# ProPrj_keero_bot_2026-04-02.net
KiCad netlist of a schematic drawn in EasyEDA Pro
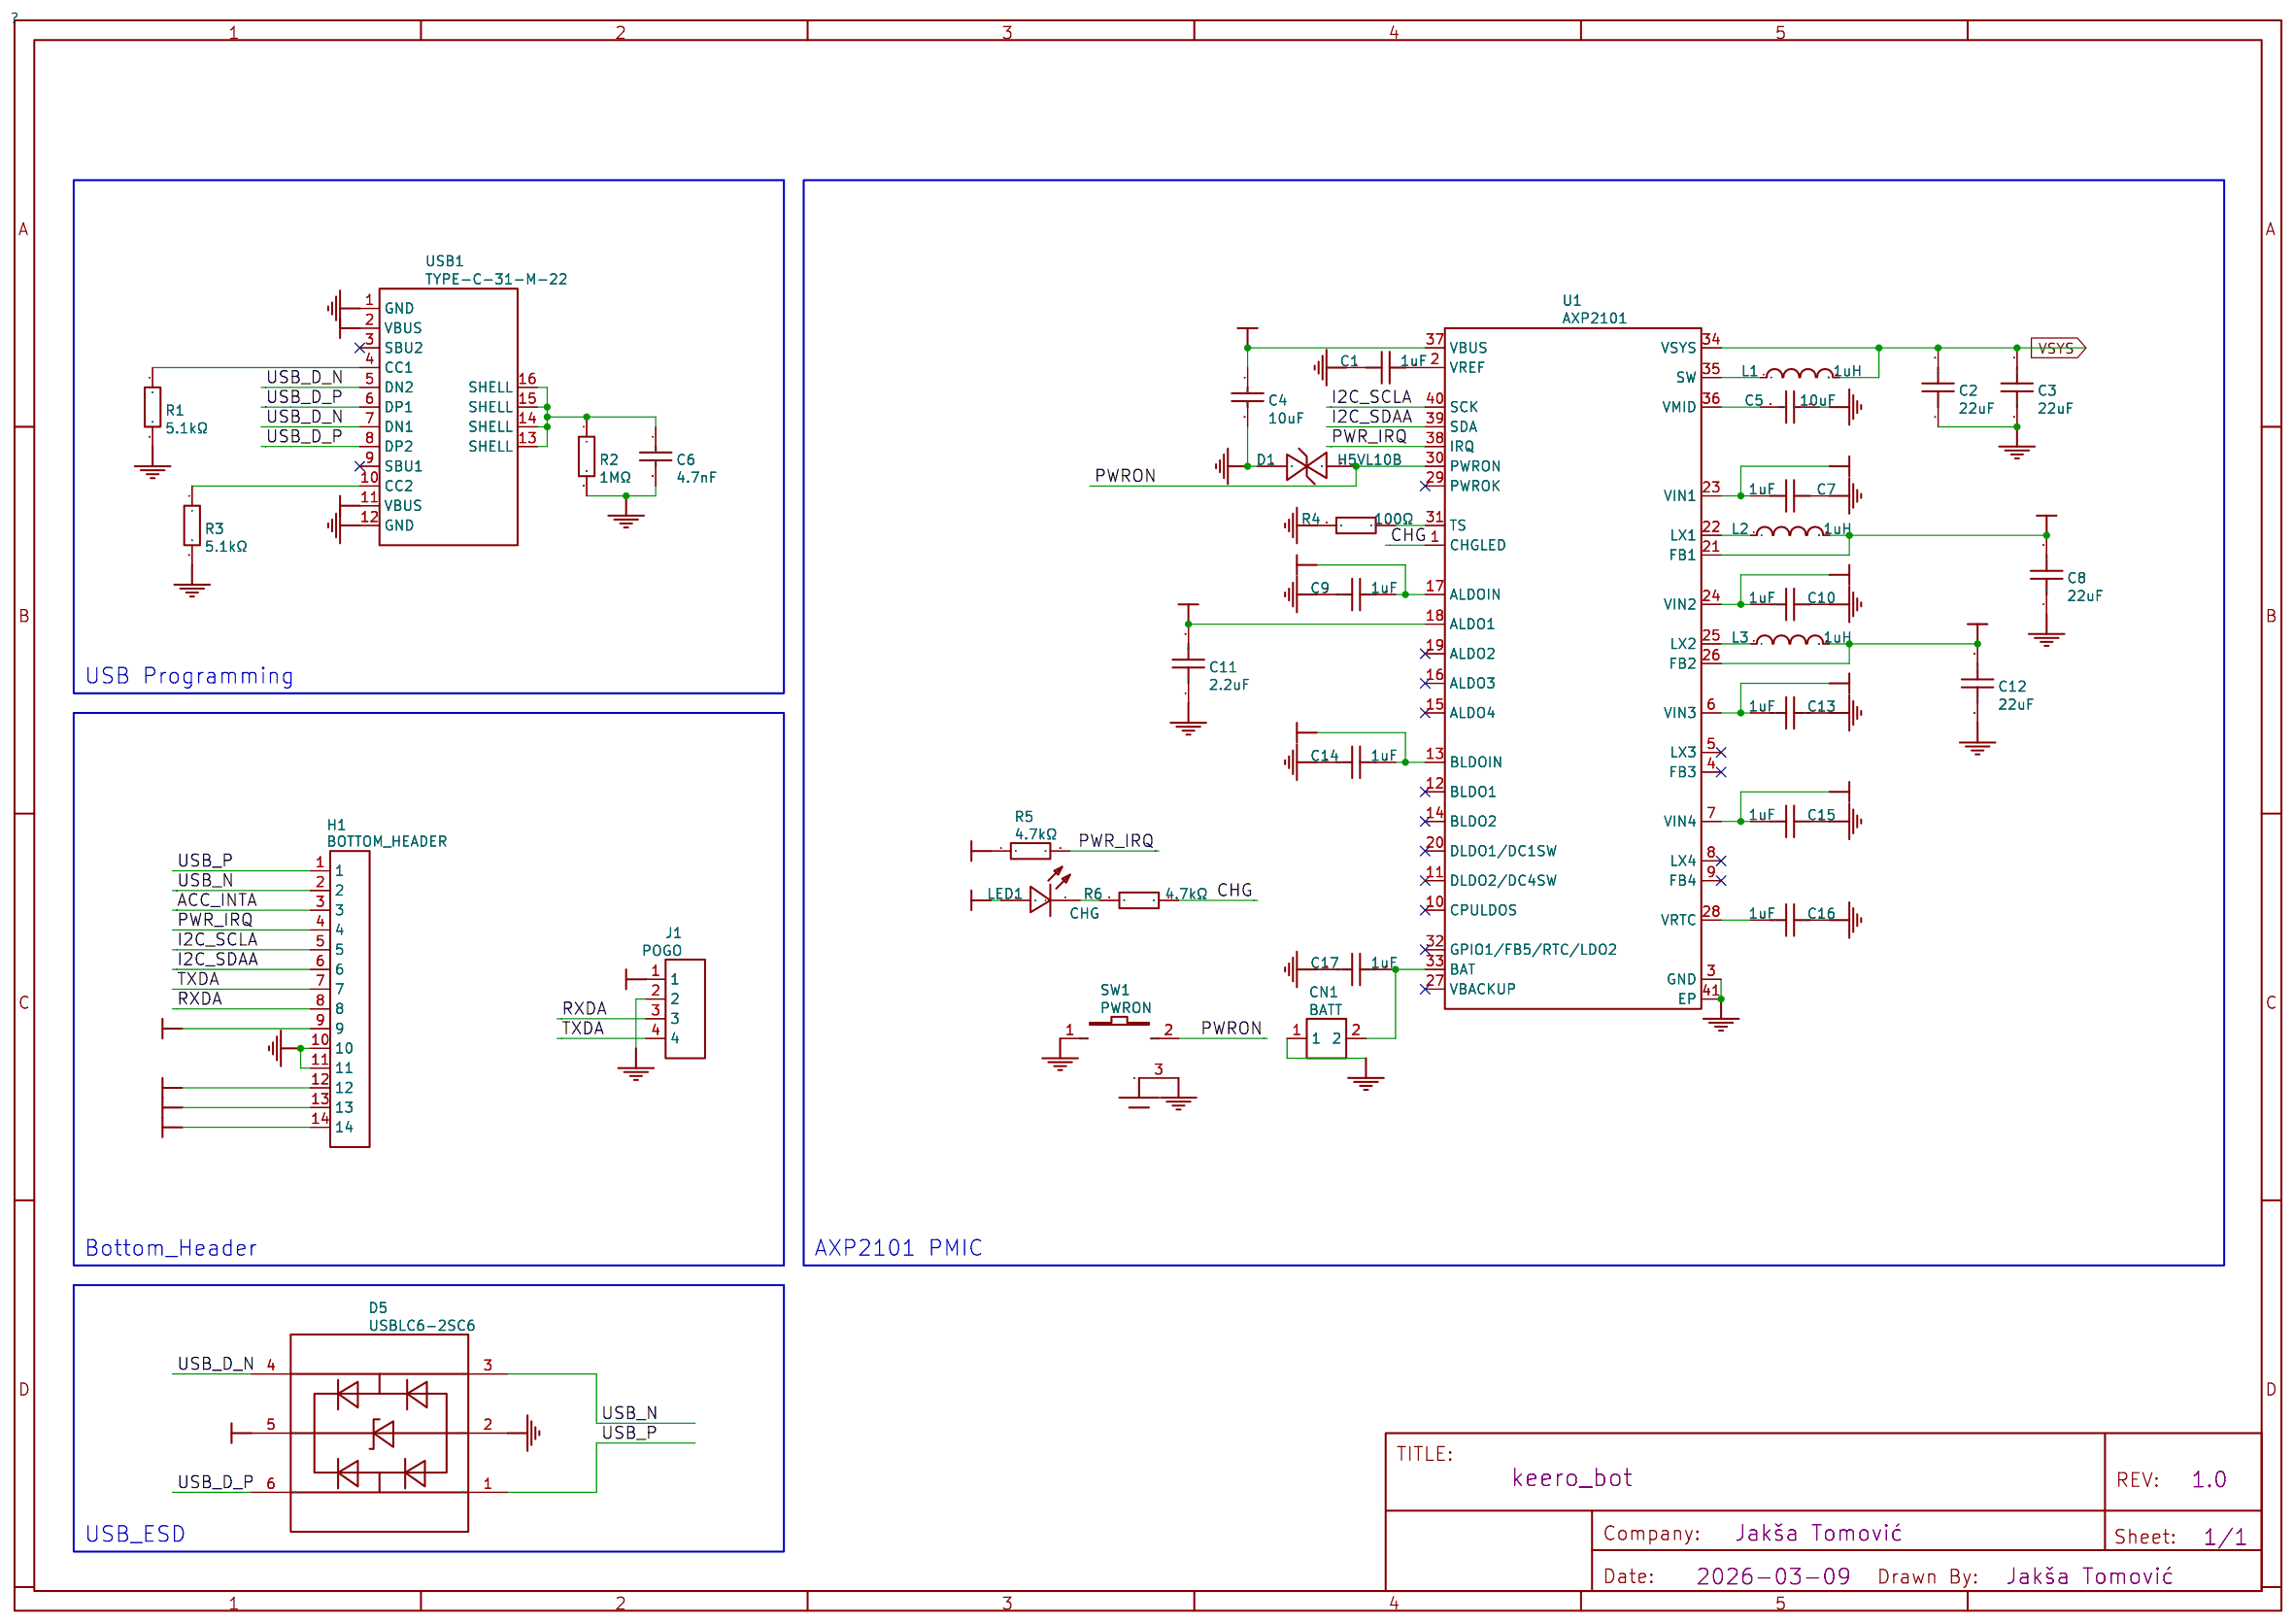
[diagram p0: Power_Sheet]
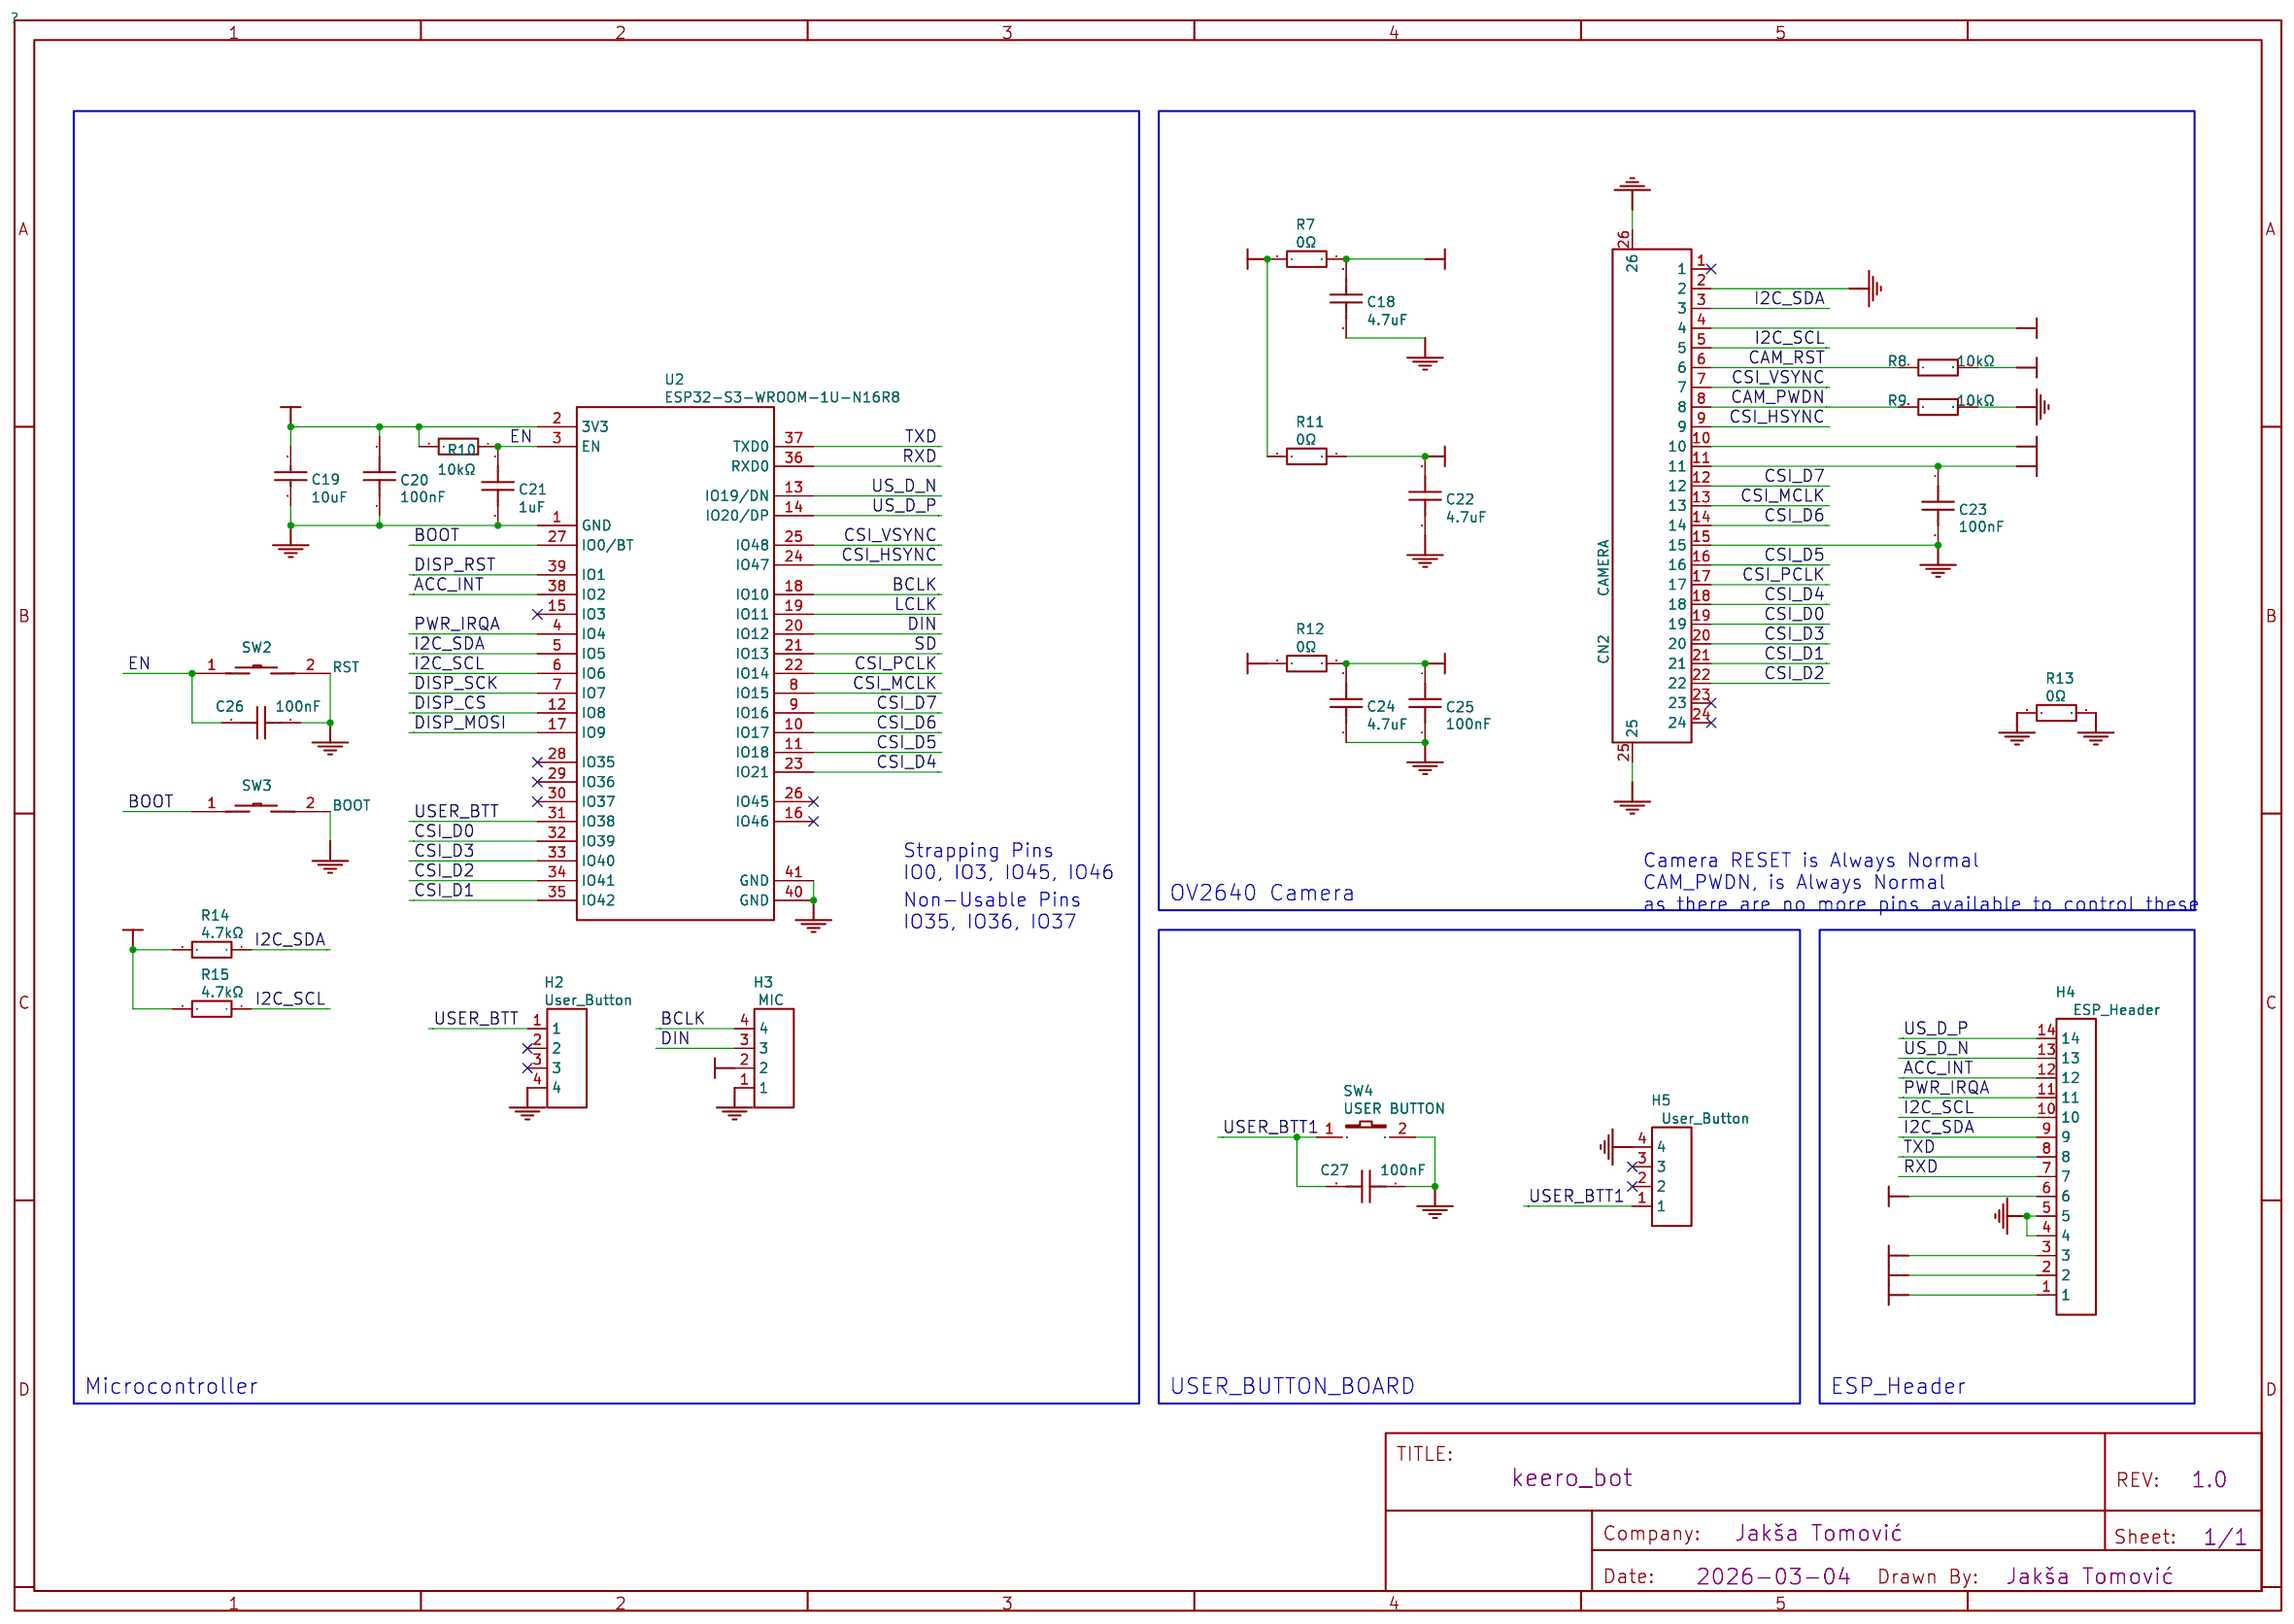
[diagram p1: MCU_Sheet]
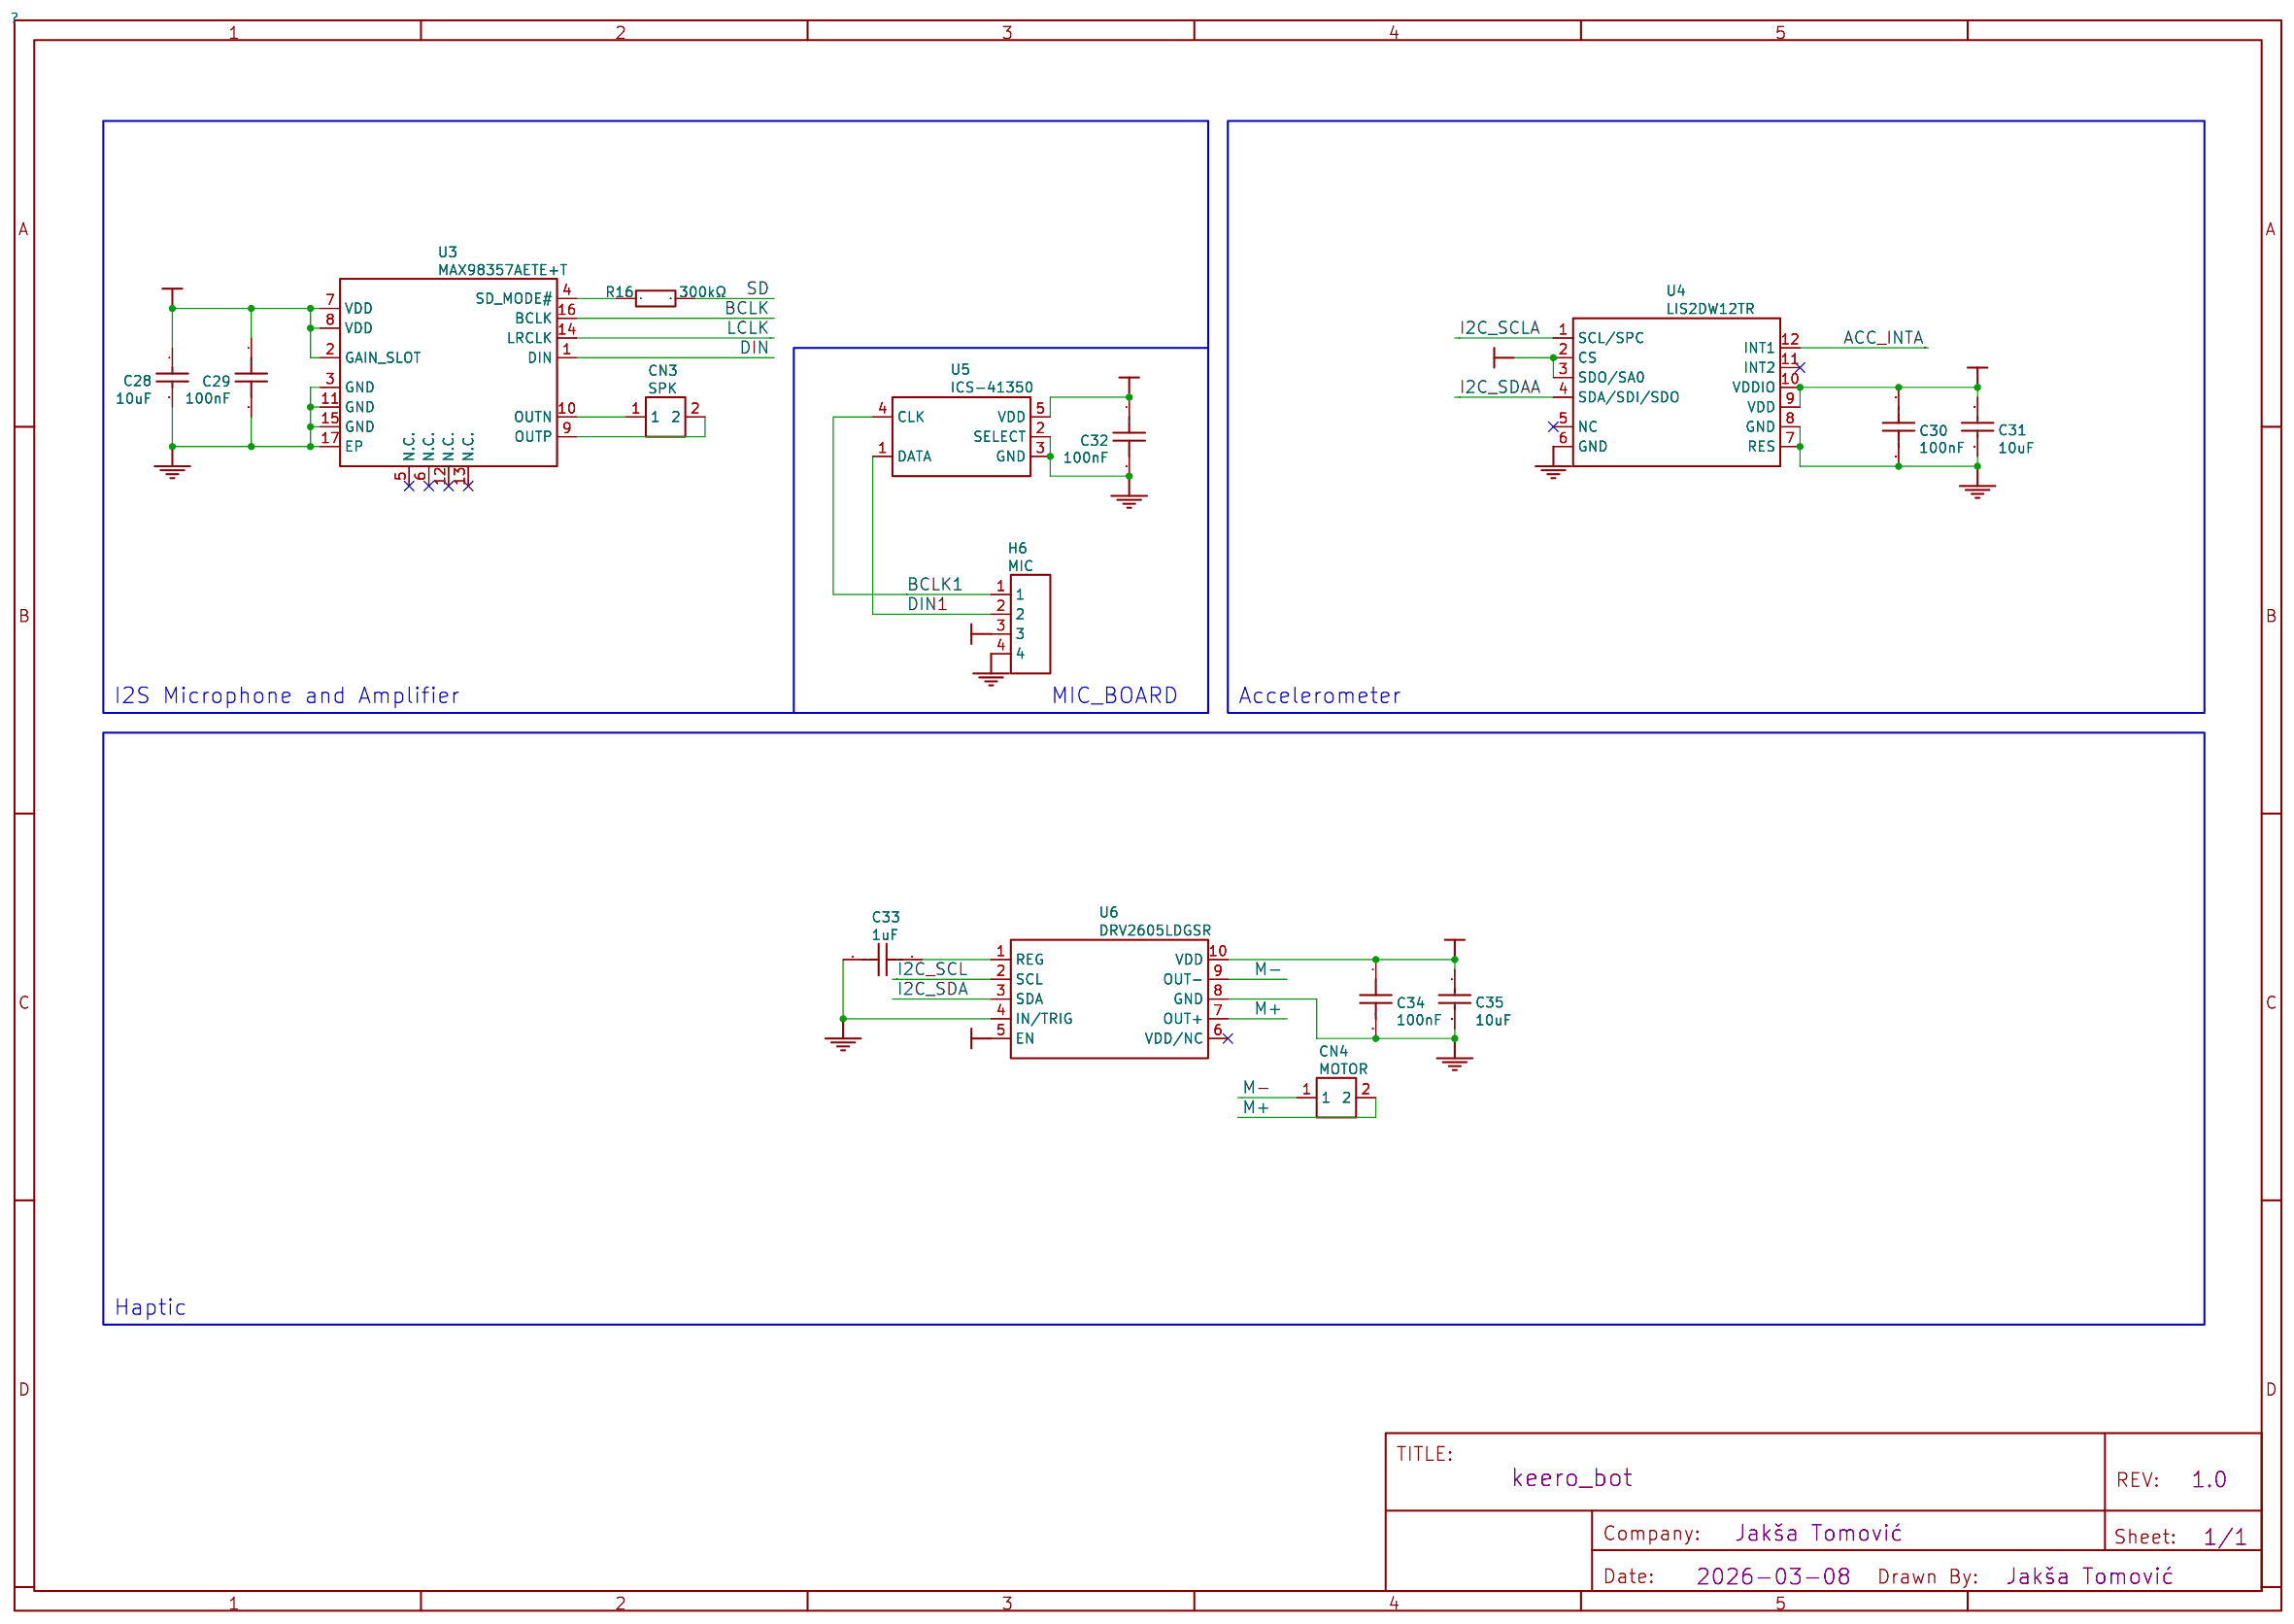
[diagram p2: Sensor_Sheet]
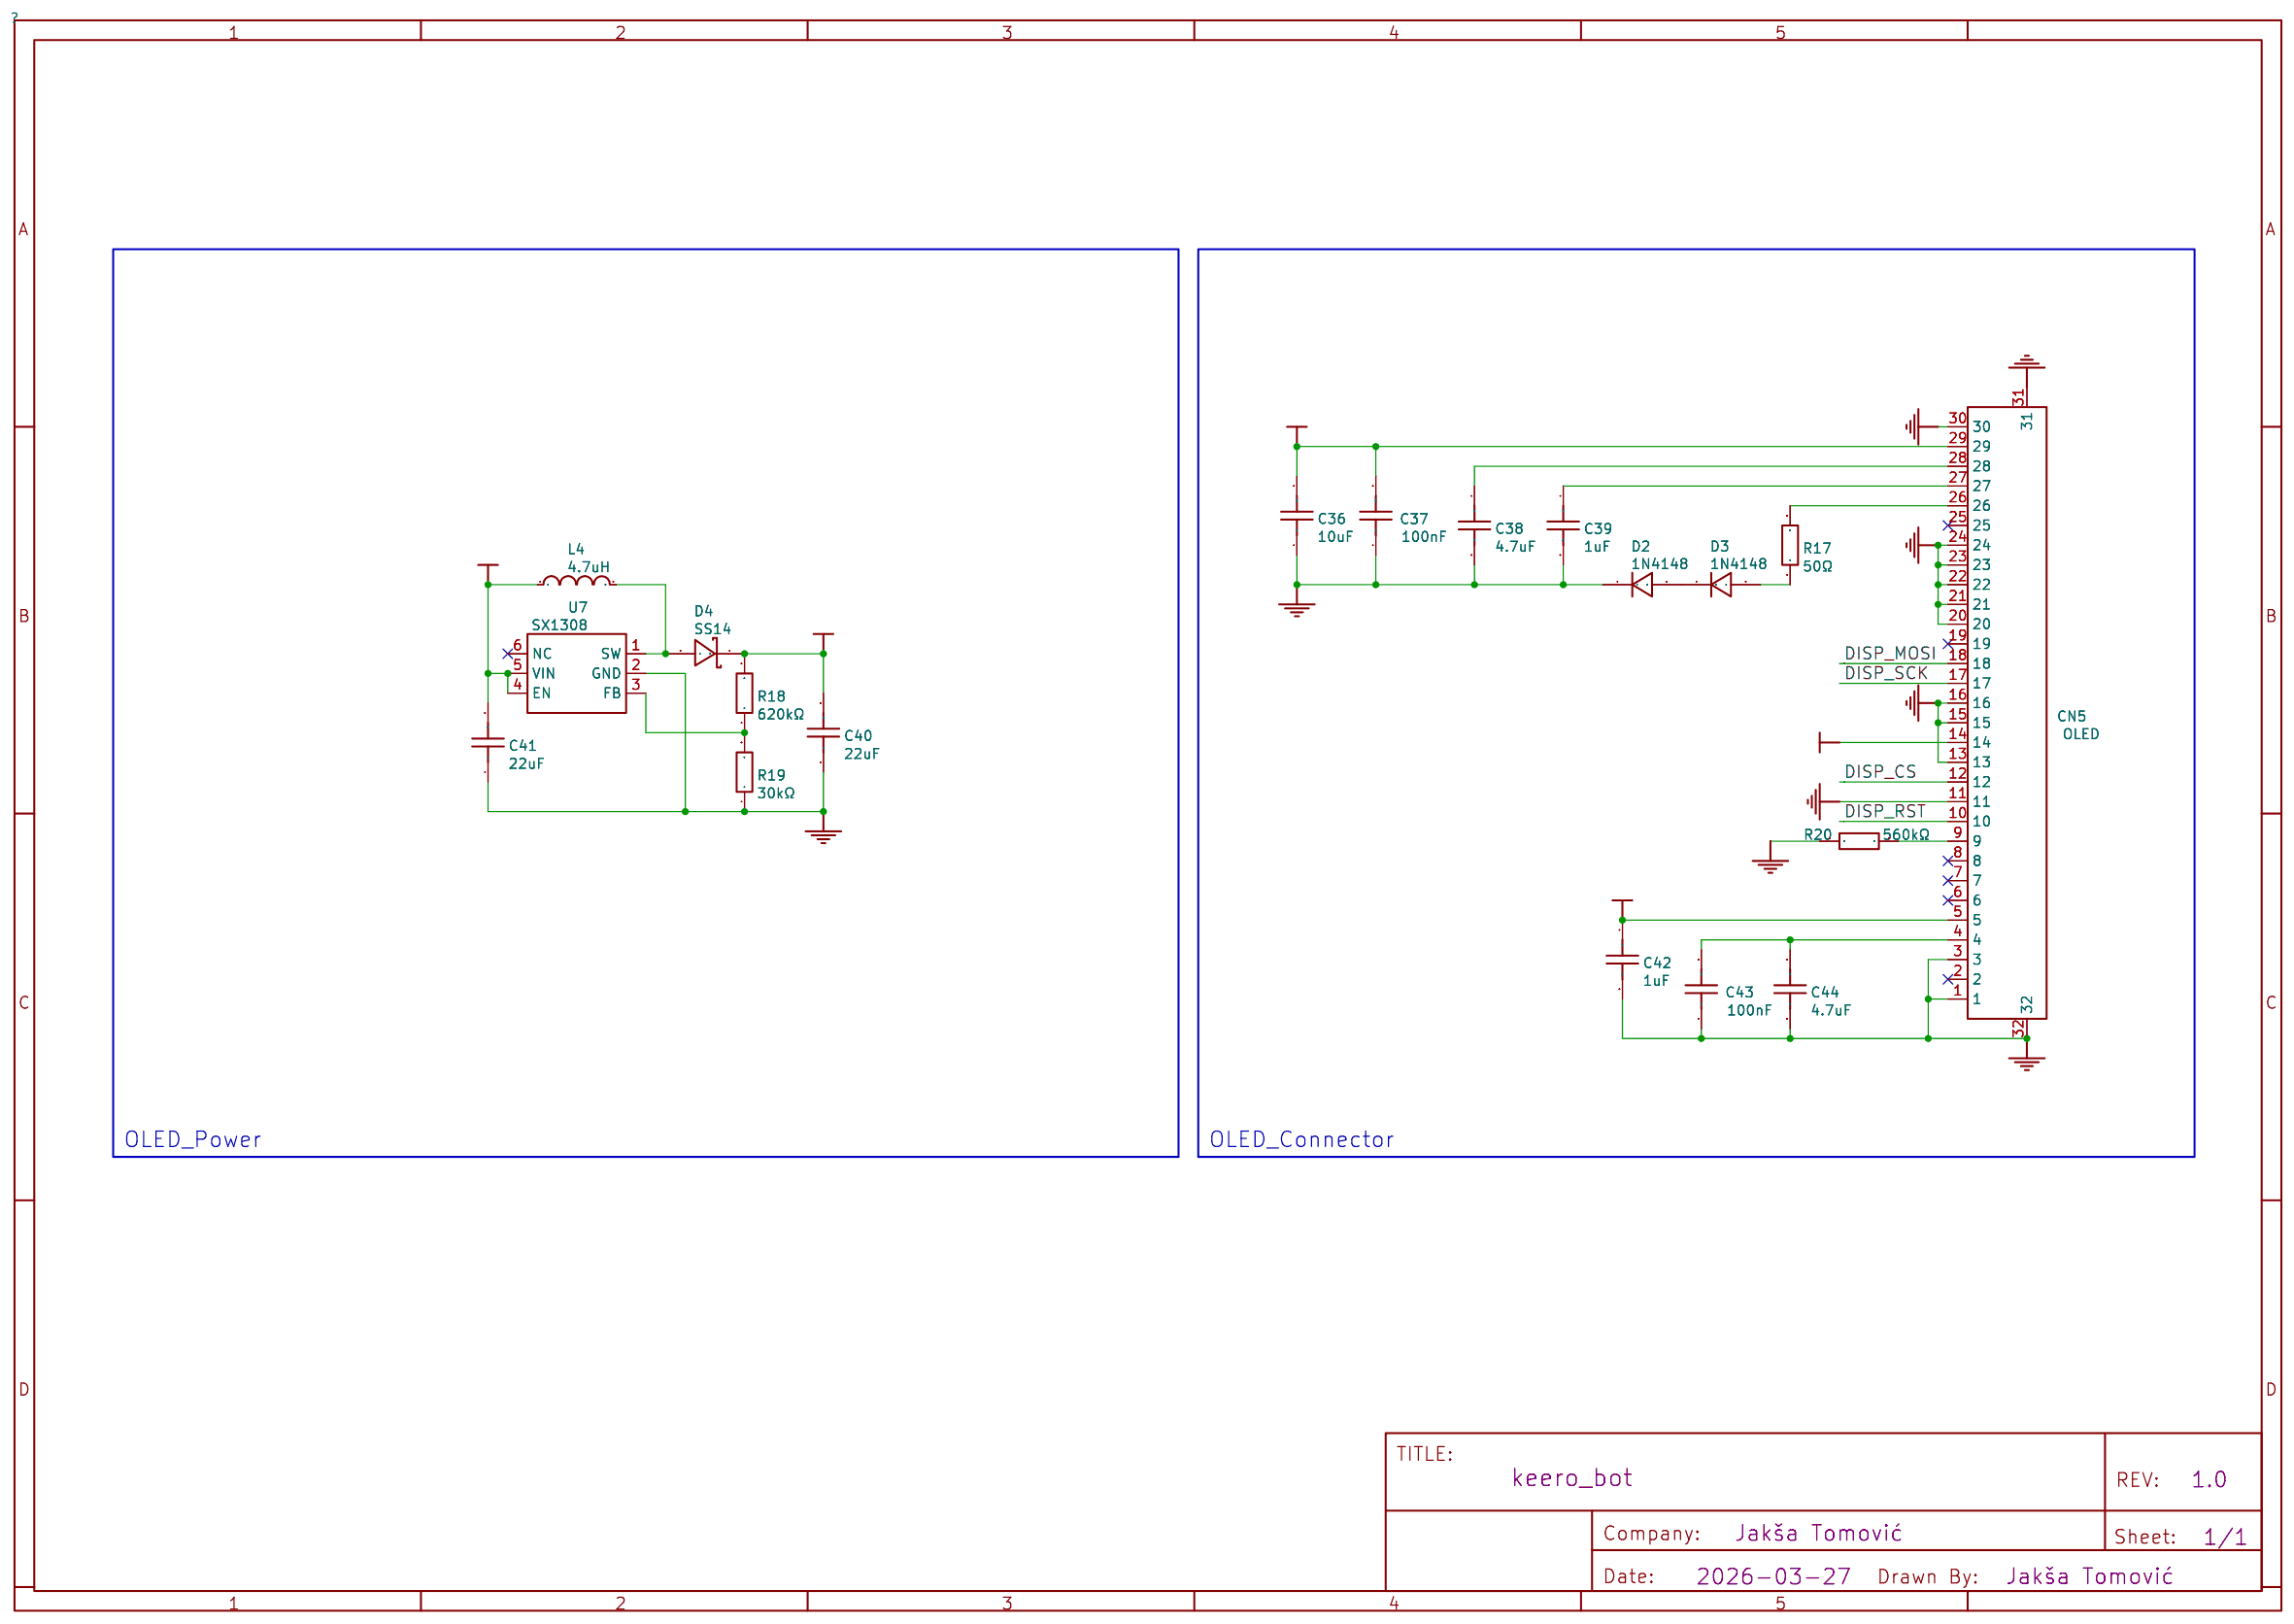
[diagram p3: OLED_Sheet]

(export (version "E")
  (design (tool "Eeschema 10.0.6"))
  (components
    (comp (ref "C1")
      (value "1uF")
      (footprint "easyedapro:C0402")
      (fields
        (field (name "Manufacturer Part") "CL05A105KA5NQNC")
        (field (name "Manufacturer") "SAMSUNG(三星)")
      )
      (libsource (lib "") (part "1uF_1"))
    )
    (comp (ref "C2")
      (value "22uF")
      (footprint "easyedapro:C0402_NEW")
      (fields
        (field (name "Manufacturer Part") "CL05A226MQ5QUNC")
        (field (name "Manufacturer") "SAMSUNG(三星)")
        (field (name "Contributor") "lcsc")
      )
      (libsource (lib "easyedapro") (part "22uF"))
    )
    (comp (ref "C3")
      (value "22uF")
      (footprint "easyedapro:C0402_NEW")
      (fields
        (field (name "Manufacturer Part") "CL05A226MQ5QUNC")
        (field (name "Manufacturer") "SAMSUNG(三星)")
        (field (name "Contributor") "lcsc")
      )
      (libsource (lib "easyedapro") (part "22uF"))
    )
    (comp (ref "C4")
      (value "10uF")
      (footprint "easyedapro:C0402")
      (fields
        (field (name "Manufacturer Part") "CL05A106MQ5NUNC")
        (field (name "Manufacturer") "SAMSUNG(三星)")
      )
      (libsource (lib "easyedapro") (part "10uF"))
    )
    (comp (ref "C5")
      (value "10uF")
      (footprint "easyedapro:C0402")
      (fields
        (field (name "Manufacturer Part") "CL05A106MQ5NUNC")
        (field (name "Manufacturer") "SAMSUNG(三星)")
      )
      (libsource (lib "easyedapro") (part "10uF"))
    )
    (comp (ref "C6")
      (value "4.7nF")
      (footprint "easyedapro:C0402")
      (fields (field (name "Manufacturer Part") "0402B472K500NT") (field (name "Manufacturer") "FH(风华)"))
      (libsource (lib "easyedapro") (part "4.7nF"))
    )
    (comp (ref "C7")
      (value "1uF")
      (footprint "easyedapro:C0402")
      (fields
        (field (name "Manufacturer Part") "CL05A105KA5NQNC")
        (field (name "Manufacturer") "SAMSUNG(三星)")
      )
      (libsource (lib "easyedapro") (part "1uF"))
    )
    (comp (ref "C8")
      (value "22uF")
      (footprint "easyedapro:C0402_NEW")
      (fields
        (field (name "Manufacturer Part") "CL05A226MQ5QUNC")
        (field (name "Manufacturer") "SAMSUNG(三星)")
        (field (name "Contributor") "lcsc")
      )
      (libsource (lib "easyedapro") (part "22uF"))
    )
    (comp (ref "C9")
      (value "1uF")
      (footprint "easyedapro:C0402")
      (fields
        (field (name "Manufacturer Part") "CL05A105KA5NQNC")
        (field (name "Manufacturer") "SAMSUNG(三星)")
      )
      (libsource (lib "") (part "1uF_1"))
    )
    (comp (ref "C10")
      (value "1uF")
      (footprint "easyedapro:C0402")
      (fields
        (field (name "Manufacturer Part") "CL05A105KA5NQNC")
        (field (name "Manufacturer") "SAMSUNG(三星)")
      )
      (libsource (lib "easyedapro") (part "1uF"))
    )
    (comp (ref "C11")
      (value "2.2uF")
      (footprint "easyedapro:C0402")
      (fields
        (field (name "Manufacturer Part") "CL05A225MQ5NSNC")
        (field (name "Manufacturer") "SAMSUNG(三星)")
      )
      (libsource (lib "easyedapro") (part "2.2uF"))
    )
    (comp (ref "C12")
      (value "22uF")
      (footprint "easyedapro:C0402_NEW")
      (fields
        (field (name "Manufacturer Part") "CL05A226MQ5QUNC")
        (field (name "Manufacturer") "SAMSUNG(三星)")
        (field (name "Contributor") "lcsc")
      )
      (libsource (lib "easyedapro") (part "22uF"))
    )
    (comp (ref "C13")
      (value "1uF")
      (footprint "easyedapro:C0402")
      (fields
        (field (name "Manufacturer Part") "CL05A105KA5NQNC")
        (field (name "Manufacturer") "SAMSUNG(三星)")
      )
      (libsource (lib "easyedapro") (part "1uF"))
    )
    (comp (ref "C14")
      (value "1uF")
      (footprint "easyedapro:C0402")
      (fields
        (field (name "Manufacturer Part") "CL05A105KA5NQNC")
        (field (name "Manufacturer") "SAMSUNG(三星)")
      )
      (libsource (lib "") (part "1uF_1"))
    )
    (comp (ref "C15")
      (value "1uF")
      (footprint "easyedapro:C0402")
      (fields
        (field (name "Manufacturer Part") "CL05A105KA5NQNC")
        (field (name "Manufacturer") "SAMSUNG(三星)")
      )
      (libsource (lib "easyedapro") (part "1uF"))
    )
    (comp (ref "C16")
      (value "1uF")
      (footprint "easyedapro:C0402")
      (fields
        (field (name "Manufacturer Part") "CL05A105KA5NQNC")
        (field (name "Manufacturer") "SAMSUNG(三星)")
      )
      (libsource (lib "easyedapro") (part "1uF"))
    )
    (comp (ref "C17")
      (value "1uF")
      (footprint "easyedapro:C0402")
      (fields
        (field (name "Manufacturer Part") "CL05A105KA5NQNC")
        (field (name "Manufacturer") "SAMSUNG(三星)")
      )
      (libsource (lib "") (part "1uF_1"))
    )
    (comp (ref "CN1")
      (value "BATT")
      (footprint "easyedapro:CONN-TH_1.25T-2AW")
      (fields
        (field (name "Manufacturer Part") "1.25T-2AW")
        (field (name "Manufacturer") "CAX(创都)")
        (field (name "Contributor") "LCSC")
      )
      (libsource (lib "easyedapro") (part "BATT"))
    )
    (comp (ref "D1")
      (value "H5VL10B")
      (footprint "easyedapro:SOD-882_L1.0-W0.6-BI")
      (fields (field (name "Manufacturer") "R+O(宏嘉诚)") (field (name "Contributor") "lcsc"))
      (libsource (lib "easyedapro") (part "H5VL10B"))
    )
    (comp (ref "D5")
      (value "USBLC6-2SC6")
      (footprint "easyedapro:SOT-23-6_L2.9-W1.6-P0.95-LS2.8-BL")
      (fields (field (name "Manufacturer") "ST(意法半导体)"))
      (libsource (lib "easyedapro") (part "USBLC6-2SC6"))
    )
    (comp (ref "H1")
      (value "BOTTOM_HEADER")
      (footprint "easyedapro:HDR-TH_14P-P1.27-H-F-W4.5-N")
      (fields
        (field (name "Manufacturer Part") "X1311FR-14-C43D24")
        (field (name "Manufacturer") "XKB Connection(中国星坤)")
        (field (name "Contributor") "LCSC")
      )
      (libsource (lib "easyedapro") (part "BOTTOM_HEADER"))
    )
    (comp (ref "J1")
      (value "POGO")
      (footprint "easyedapro:POGO CONTACT 2")
      (fields (field (name "Contributor") "shaikhabdulmobeen"))
      (libsource (lib "easyedapro") (part "POGO"))
    )
    (comp (ref "L1")
      (value "1uH")
      (footprint "easyedapro:L0805")
      (fields (field (name "Manufacturer Part") "MPL2012S1R0MHT") (field (name "Manufacturer") "Sunlord(顺络)"))
      (libsource (lib "easyedapro") (part "1uH"))
    )
    (comp (ref "L2")
      (value "1uH")
      (footprint "easyedapro:L0805")
      (fields (field (name "Manufacturer Part") "MPL2012S1R0MHT") (field (name "Manufacturer") "Sunlord(顺络)"))
      (libsource (lib "easyedapro") (part "1uH"))
    )
    (comp (ref "L3")
      (value "1uH")
      (footprint "easyedapro:L0805")
      (fields (field (name "Manufacturer Part") "MPL2012S1R0MHT") (field (name "Manufacturer") "Sunlord(顺络)"))
      (libsource (lib "easyedapro") (part "1uH"))
    )
    (comp (ref "LED1")
      (value "CHG")
      (footprint "easyedapro:LED0603-RD")
      (fields (field (name "Manufacturer Part") "KT-0603R") (field (name "Manufacturer") "KENTO"))
      (libsource (lib "easyedapro") (part "CHG"))
    )
    (comp (ref "R1")
      (value "5.1kΩ")
      (footprint "easyedapro:R0402")
      (fields
        (field (name "Manufacturer Part") "0402WGF5101TCE")
        (field (name "Manufacturer") "UNI-ROYAL(厚声)")
      )
      (libsource (lib "easyedapro") (part "5.1kΩ"))
    )
    (comp (ref "R2")
      (value "1MΩ")
      (footprint "easyedapro:R0402")
      (fields
        (field (name "Manufacturer Part") "0402WGF1004TCE")
        (field (name "Manufacturer") "UNI-ROYAL(厚声)")
      )
      (libsource (lib "easyedapro") (part "1MΩ"))
    )
    (comp (ref "R3")
      (value "5.1kΩ")
      (footprint "easyedapro:R0402")
      (fields
        (field (name "Manufacturer Part") "0402WGF5101TCE")
        (field (name "Manufacturer") "UNI-ROYAL(厚声)")
      )
      (libsource (lib "easyedapro") (part "5.1kΩ"))
    )
    (comp (ref "R4")
      (value "100Ω")
      (footprint "easyedapro:R0402")
      (fields
        (field (name "Manufacturer Part") "0402WGF1000TCE")
        (field (name "Manufacturer") "UNI-ROYAL(厚声)")
      )
      (libsource (lib "easyedapro") (part "100Ω"))
    )
    (comp (ref "R5")
      (value "4.7kΩ")
      (footprint "easyedapro:R0402")
      (fields
        (field (name "Manufacturer Part") "0402WGF4701TCE")
        (field (name "Manufacturer") "UNI-ROYAL(厚声)")
      )
      (libsource (lib "") (part "4.7kΩ_1"))
    )
    (comp (ref "R6")
      (value "4.7kΩ")
      (footprint "easyedapro:R0402")
      (fields
        (field (name "Manufacturer Part") "0402WGF4701TCE")
        (field (name "Manufacturer") "UNI-ROYAL(厚声)")
      )
      (libsource (lib "easyedapro") (part "4.7kΩ"))
    )
    (comp (ref "SW1")
      (value "PWRON")
      (footprint "easyedapro:KEY-TH_K2-1109DE-CXXW-XX")
      (fields
        (field (name "Manufacturer Part") "K2-1109DE-A4SW-01")
        (field (name "Manufacturer") "韩国韩荣")
        (field (name "Contributor") "LCSC")
      )
      (libsource (lib "easyedapro") (part "PWRON"))
    )
    (comp (ref "U1")
      (value "AXP2101")
      (footprint "easyedapro:QFN-40_L5.0-W5.0-P0.40-TL-EP3.4")
      (fields (field (name "Manufacturer") "x-powers") (field (name "Contributor") "shaikhabdulmobeen"))
      (libsource (lib "easyedapro") (part "AXP2101"))
    )
    (comp (ref "USB1")
      (value "TYPE-C-31-M-22")
      (footprint "easyedapro:USB-C-SMD_TYPE-C-31-M-22")
      (fields (field (name "Manufacturer") "韩国韩荣") (field (name "Contributor") "LCSC"))
      (libsource (lib "easyedapro") (part "TYPE-C-31-M-22"))
    )
    (comp (ref "C18")
      (value "4.7uF")
      (footprint "easyedapro:C0402_NEW")
      (fields
        (field (name "Manufacturer Part") "CL05A475MP5NRNC")
        (field (name "Manufacturer") "SAMSUNG(三星)")
      )
      (libsource (lib "easyedapro") (part "4.7uF"))
    )
    (comp (ref "C19")
      (value "10uF")
      (footprint "easyedapro:C0402")
      (fields
        (field (name "Manufacturer Part") "CL05A106MQ5NUNC")
        (field (name "Manufacturer") "SAMSUNG(三星)")
      )
      (libsource (lib "easyedapro") (part "10uF"))
    )
    (comp (ref "C20")
      (value "100nF")
      (footprint "easyedapro:C0402")
      (fields
        (field (name "Manufacturer Part") "CL05B104KB54PNC")
        (field (name "Manufacturer") "SAMSUNG(三星)")
        (field (name "Contributor") "LCSC")
      )
      (libsource (lib "easyedapro") (part "100nF"))
    )
    (comp (ref "C21")
      (value "1uF")
      (footprint "easyedapro:C0402")
      (fields
        (field (name "Manufacturer Part") "CL05A105KA5NQNC")
        (field (name "Manufacturer") "SAMSUNG(三星)")
      )
      (libsource (lib "easyedapro") (part "1uF"))
    )
    (comp (ref "C22")
      (value "4.7uF")
      (footprint "easyedapro:C0402_NEW")
      (fields
        (field (name "Manufacturer Part") "CL05A475MP5NRNC")
        (field (name "Manufacturer") "SAMSUNG(三星)")
      )
      (libsource (lib "easyedapro") (part "4.7uF"))
    )
    (comp (ref "C23")
      (value "100nF")
      (footprint "easyedapro:C0402")
      (fields
        (field (name "Manufacturer Part") "CL05B104KB54PNC")
        (field (name "Manufacturer") "SAMSUNG(三星)")
        (field (name "Contributor") "LCSC")
      )
      (libsource (lib "easyedapro") (part "100nF"))
    )
    (comp (ref "C24")
      (value "4.7uF")
      (footprint "easyedapro:C0402_NEW")
      (fields
        (field (name "Manufacturer Part") "CL05A475MP5NRNC")
        (field (name "Manufacturer") "SAMSUNG(三星)")
      )
      (libsource (lib "easyedapro") (part "4.7uF"))
    )
    (comp (ref "C25")
      (value "100nF")
      (footprint "easyedapro:C0402")
      (fields
        (field (name "Manufacturer Part") "CL05B104KB54PNC")
        (field (name "Manufacturer") "SAMSUNG(三星)")
        (field (name "Contributor") "LCSC")
      )
      (libsource (lib "easyedapro") (part "100nF"))
    )
    (comp (ref "C26")
      (value "100nF")
      (footprint "easyedapro:C0402")
      (fields
        (field (name "Manufacturer Part") "CL05B104KB54PNC")
        (field (name "Manufacturer") "SAMSUNG(三星)")
        (field (name "Contributor") "LCSC")
      )
      (libsource (lib "easyedapro") (part "100nF"))
    )
    (comp (ref "C27")
      (value "100nF")
      (footprint "easyedapro:C0402")
      (fields
        (field (name "Manufacturer Part") "CL05B104KB54PNC")
        (field (name "Manufacturer") "SAMSUNG(三星)")
        (field (name "Contributor") "LCSC")
      )
      (libsource (lib "easyedapro") (part "100nF"))
    )
    (comp (ref "CN2")
      (value "CAMERA")
      (footprint "easyedapro:FPC-SMD_KH-FG0.5-H2.0-24PIN")
      (fields
        (field (name "Manufacturer Part") "KH-FG0.5-H2.0-24PIN")
        (field (name "Manufacturer") "kinghelm(金航标)")
        (field (name "Contributor") "LCSC")
      )
      (libsource (lib "easyedapro") (part "CAMERA"))
    )
    (comp (ref "H2")
      (value "User_Button")
      (footprint "easyedapro:HDR-TH_4P-P1.27-V-M")
      (fields
        (field (name "Manufacturer Part") "X1311WV-04J-C18D27")
        (field (name "Manufacturer") "XKB Connection(中国星坤)")
        (field (name "Contributor") "LCSC")
      )
      (libsource (lib "easyedapro") (part "User_Button"))
    )
    (comp (ref "H3")
      (value "MIC")
      (footprint "easyedapro:HDR-TH_4P-P1.27-V-M")
      (fields
        (field (name "Manufacturer Part") "X1311WV-04J-C18D27")
        (field (name "Manufacturer") "XKB Connection(中国星坤)")
        (field (name "Contributor") "LCSC")
      )
      (libsource (lib "easyedapro") (part "MIC"))
    )
    (comp (ref "H4")
      (value "ESP_Header")
      (footprint "easyedapro:HDR-TH_14P-P1.27-V-M")
      (fields
        (field (name "Manufacturer Part") "X1311WV-14J-C18D27")
        (field (name "Manufacturer") "XKB Connection(中国星坤)")
        (field (name "Contributor") "LCSC")
      )
      (libsource (lib "easyedapro") (part "ESP_Header"))
    )
    (comp (ref "H5")
      (value "User_Button")
      (footprint "easyedapro:HDR-TH_4P-P1.27-H-F-W4.5-N")
      (fields
        (field (name "Manufacturer Part") "X1311FR-04-C43D24")
        (field (name "Manufacturer") "XKB Connection(中国星坤)")
        (field (name "Contributor") "LCSC")
      )
      (libsource (lib "") (part "User_Button_1"))
    )
    (comp (ref "R7")
      (value "0Ω")
      (footprint "easyedapro:R0402")
      (fields
        (field (name "Manufacturer Part") "0402WGF0000TCE")
        (field (name "Manufacturer") "UNI-ROYAL(厚声)")
      )
      (libsource (lib "easyedapro") (part "0Ω"))
    )
    (comp (ref "R8")
      (value "10kΩ")
      (footprint "easyedapro:R0402")
      (fields
        (field (name "Manufacturer Part") "0402WGF1002TCE")
        (field (name "Manufacturer") "UNI-ROYAL(厚声)")
      )
      (libsource (lib "") (part "10kΩ_1"))
    )
    (comp (ref "R9")
      (value "10kΩ")
      (footprint "easyedapro:R0402")
      (fields
        (field (name "Manufacturer Part") "0402WGF1002TCE")
        (field (name "Manufacturer") "UNI-ROYAL(厚声)")
      )
      (libsource (lib "") (part "10kΩ_1"))
    )
    (comp (ref "R10")
      (value "10kΩ")
      (footprint "easyedapro:R0402")
      (fields
        (field (name "Manufacturer Part") "0402WGF1002TCE")
        (field (name "Manufacturer") "UNI-ROYAL(厚声)")
      )
      (libsource (lib "easyedapro") (part "10kΩ"))
    )
    (comp (ref "R11")
      (value "0Ω")
      (footprint "easyedapro:R0402")
      (fields
        (field (name "Manufacturer Part") "0402WGF0000TCE")
        (field (name "Manufacturer") "UNI-ROYAL(厚声)")
      )
      (libsource (lib "easyedapro") (part "0Ω"))
    )
    (comp (ref "R12")
      (value "0Ω")
      (footprint "easyedapro:R0402")
      (fields
        (field (name "Manufacturer Part") "0402WGF0000TCE")
        (field (name "Manufacturer") "UNI-ROYAL(厚声)")
      )
      (libsource (lib "easyedapro") (part "0Ω"))
    )
    (comp (ref "R13")
      (value "0Ω")
      (footprint "easyedapro:R0402")
      (fields
        (field (name "Manufacturer Part") "0402WGF0000TCE")
        (field (name "Manufacturer") "UNI-ROYAL(厚声)")
      )
      (libsource (lib "easyedapro") (part "0Ω"))
    )
    (comp (ref "R14")
      (value "4.7kΩ")
      (footprint "easyedapro:R0402")
      (fields
        (field (name "Manufacturer Part") "0402WGF4701TCE")
        (field (name "Manufacturer") "UNI-ROYAL(厚声)")
      )
      (libsource (lib "easyedapro") (part "4.7kΩ"))
    )
    (comp (ref "R15")
      (value "4.7kΩ")
      (footprint "easyedapro:R0402")
      (fields
        (field (name "Manufacturer Part") "0402WGF4701TCE")
        (field (name "Manufacturer") "UNI-ROYAL(厚声)")
      )
      (libsource (lib "easyedapro") (part "4.7kΩ"))
    )
    (comp (ref "SW2")
      (value "RST")
      (footprint "easyedapro:KEY-SMD_B3U-1000PM")
      (fields
        (field (name "Manufacturer Part") "B3U-1000P")
        (field (name "Manufacturer") "OMRON(欧姆龙)")
        (field (name "Contributor") "LCSC")
      )
      (libsource (lib "easyedapro") (part "RST"))
    )
    (comp (ref "SW3")
      (value "BOOT")
      (footprint "easyedapro:KEY-SMD_B3U-1000PM")
      (fields
        (field (name "Manufacturer Part") "B3U-1000P")
        (field (name "Manufacturer") "OMRON(欧姆龙)")
        (field (name "Contributor") "LCSC")
      )
      (libsource (lib "easyedapro") (part "BOOT"))
    )
    (comp (ref "SW4")
      (value "USER BUTTON")
      (footprint "easyedapro:KEY-SMD_2P-L6.2-W3.6-LS8.0")
      (fields (field (name "Manufacturer Part") "K2-1107ST-A4SW-06") (field (name "Contributor") "LCEDA_Lib"))
      (libsource (lib "easyedapro") (part "USER BUTTON"))
    )
    (comp (ref "U2")
      (value "ESP32-S3-WROOM-1U-N16R8")
      (footprint "easyedapro:WIRELM-SMD_ESP32-S3-WROOM-1U")
      (fields (field (name "Manufacturer") "ESPRESSIF(乐鑫)") (field (name "Contributor") "shaikhabdulmobeen"))
      (libsource (lib "easyedapro") (part "ESP32-S3-WROOM-1U-N16R8"))
    )
    (comp (ref "C28")
      (value "10uF")
      (footprint "easyedapro:C0402")
      (fields
        (field (name "Manufacturer Part") "CL05A106MQ5NUNC")
        (field (name "Manufacturer") "SAMSUNG(三星)")
      )
      (libsource (lib "") (part "10uF_1"))
    )
    (comp (ref "C29")
      (value "100nF")
      (footprint "easyedapro:C0402")
      (fields
        (field (name "Manufacturer Part") "CL05B104KB54PNC")
        (field (name "Manufacturer") "SAMSUNG(三星)")
        (field (name "Contributor") "LCSC")
      )
      (libsource (lib "") (part "100nF_1"))
    )
    (comp (ref "C30")
      (value "100nF")
      (footprint "easyedapro:C0402")
      (fields
        (field (name "Manufacturer Part") "CL05B104KB54PNC")
        (field (name "Manufacturer") "SAMSUNG(三星)")
        (field (name "Contributor") "LCSC")
      )
      (libsource (lib "easyedapro") (part "100nF"))
    )
    (comp (ref "C31")
      (value "10uF")
      (footprint "easyedapro:C0402")
      (fields
        (field (name "Manufacturer Part") "CL05A106MQ5NUNC")
        (field (name "Manufacturer") "SAMSUNG(三星)")
      )
      (libsource (lib "easyedapro") (part "10uF"))
    )
    (comp (ref "C32")
      (value "100nF")
      (footprint "easyedapro:C0402")
      (fields
        (field (name "Manufacturer Part") "CL05B104KB54PNC")
        (field (name "Manufacturer") "SAMSUNG(三星)")
        (field (name "Contributor") "LCSC")
      )
      (libsource (lib "") (part "100nF_1"))
    )
    (comp (ref "C33")
      (value "1uF")
      (footprint "easyedapro:C0402")
      (fields
        (field (name "Manufacturer Part") "CL05A105KA5NQNC")
        (field (name "Manufacturer") "SAMSUNG(三星)")
      )
      (libsource (lib "easyedapro") (part "1uF"))
    )
    (comp (ref "C34")
      (value "100nF")
      (footprint "easyedapro:C0402")
      (fields
        (field (name "Manufacturer Part") "CL05B104KB54PNC")
        (field (name "Manufacturer") "SAMSUNG(三星)")
        (field (name "Contributor") "LCSC")
      )
      (libsource (lib "easyedapro") (part "100nF"))
    )
    (comp (ref "C35")
      (value "10uF")
      (footprint "easyedapro:C0402")
      (fields
        (field (name "Manufacturer Part") "CL05A106MQ5NUNC")
        (field (name "Manufacturer") "SAMSUNG(三星)")
      )
      (libsource (lib "easyedapro") (part "10uF"))
    )
    (comp (ref "CN3")
      (value "SPK")
      (footprint "easyedapro:CONN-TH_1.25T-2AW")
      (fields
        (field (name "Manufacturer Part") "1.25T-2AW")
        (field (name "Manufacturer") "CAX(创都)")
        (field (name "Contributor") "LCSC")
      )
      (libsource (lib "easyedapro") (part "SPK"))
    )
    (comp (ref "CN4")
      (value "MOTOR")
      (footprint "easyedapro:CONN-TH_1.25T-2AW")
      (fields
        (field (name "Manufacturer Part") "1.25T-2AW")
        (field (name "Manufacturer") "CAX(创都)")
        (field (name "Contributor") "LCSC")
      )
      (libsource (lib "easyedapro") (part "MOTOR"))
    )
    (comp (ref "H6")
      (value "MIC")
      (footprint "easyedapro:HDR-TH_4P-P1.27-H-F-W4.5-N")
      (fields
        (field (name "Manufacturer Part") "X1311FR-04-C43D24")
        (field (name "Manufacturer") "XKB Connection(中国星坤)")
        (field (name "Contributor") "LCSC")
      )
      (libsource (lib "easyedapro") (part "MIC"))
    )
    (comp (ref "R16")
      (value "300kΩ")
      (footprint "easyedapro:R0402")
      (fields
        (field (name "Manufacturer Part") "0402WGF3003TCE")
        (field (name "Manufacturer") "UNI-ROYAL(厚声)")
      )
      (libsource (lib "easyedapro") (part "300kΩ"))
    )
    (comp (ref "U3")
      (value "MAX98357AETE+T")
      (footprint "easyedapro:TQFN-16_L3.0-W3.0-P0.50-BL-EP1.5")
      (fields
        (field (name "Manufacturer") "ADI(亚德诺)/MAXIM(美信)")
        (field (name "Contributor") "shaikhabdulmobeen")
      )
      (libsource (lib "easyedapro") (part "MAX98357AETE+T"))
    )
    (comp (ref "U4")
      (value "LIS2DW12TR")
      (footprint "easyedapro:LGA-12_L2.0-W2.0-P0.50-BL")
      (fields (field (name "Manufacturer") "ST(意法半导体)") (field (name "Contributor") "LCSC"))
      (libsource (lib "easyedapro") (part "LIS2DW12TR"))
    )
    (comp (ref "U5")
      (value "ICS-41350")
      (footprint "easyedapro:MIC-SMD_5P-L3.5-W2.7-TL")
      (fields
        (field (name "Manufacturer") "TDK InvenSense(应美盛)")
        (field (name "Contributor") "shaikhabdulmobeen")
      )
      (libsource (lib "easyedapro") (part "ICS-41350"))
    )
    (comp (ref "U6")
      (value "DRV2605LDGSR")
      (footprint "easyedapro:VSSOP-10_L3.0-W3.0-P0.50-LS4.9-BL")
      (fields (field (name "Manufacturer") "TI(德州仪器)") (field (name "Contributor") "LCSC"))
      (libsource (lib "easyedapro") (part "DRV2605LDGSR"))
    )
    (comp (ref "C36")
      (value "10uF")
      (footprint "easyedapro:C0603")
      (fields
        (field (name "Manufacturer Part") "CL10A106MA8NRNC")
        (field (name "Manufacturer") "SAMSUNG(三星)")
      )
      (libsource (lib "easyedapro") (part "10uF"))
    )
    (comp (ref "C37")
      (value "100nF")
      (footprint "easyedapro:C0402")
      (fields
        (field (name "Manufacturer Part") "CL05B104KB54PNC")
        (field (name "Manufacturer") "SAMSUNG(三星)")
        (field (name "Contributor") "LCSC")
      )
      (libsource (lib "easyedapro") (part "100nF"))
    )
    (comp (ref "C38")
      (value "4.7uF")
      (footprint "easyedapro:C0402_NEW")
      (fields
        (field (name "Manufacturer Part") "CL05A475MO5NUNC")
        (field (name "Manufacturer") "SAMSUNG(三星)")
        (field (name "Contributor") "LCSC")
      )
      (libsource (lib "easyedapro") (part "4.7uF"))
    )
    (comp (ref "C39")
      (value "1uF")
      (footprint "easyedapro:C0402")
      (fields
        (field (name "Manufacturer Part") "CL05A105KA5NQNC")
        (field (name "Manufacturer") "SAMSUNG(三星)")
      )
      (libsource (lib "easyedapro") (part "1uF"))
    )
    (comp (ref "C40")
      (value "22uF")
      (footprint "easyedapro:C0402_NEW")
      (fields
        (field (name "Manufacturer Part") "CL05A226MQ5QUNC")
        (field (name "Manufacturer") "SAMSUNG(三星)")
      )
      (libsource (lib "easyedapro") (part "22uF"))
    )
    (comp (ref "C41")
      (value "22uF")
      (footprint "easyedapro:C0402_NEW")
      (fields
        (field (name "Manufacturer Part") "CL05A226MQ5QUNC")
        (field (name "Manufacturer") "SAMSUNG(三星)")
      )
      (libsource (lib "easyedapro") (part "22uF"))
    )
    (comp (ref "C42")
      (value "1uF")
      (footprint "easyedapro:C0402")
      (fields
        (field (name "Manufacturer Part") "CL05A105KA5NQNC")
        (field (name "Manufacturer") "SAMSUNG(三星)")
      )
      (libsource (lib "easyedapro") (part "1uF"))
    )
    (comp (ref "C43")
      (value "100nF")
      (footprint "easyedapro:C0402")
      (fields
        (field (name "Manufacturer Part") "CL05B104KB54PNC")
        (field (name "Manufacturer") "SAMSUNG(三星)")
        (field (name "Contributor") "LCSC")
      )
      (libsource (lib "easyedapro") (part "100nF"))
    )
    (comp (ref "C44")
      (value "4.7uF")
      (footprint "easyedapro:C0402_NEW")
      (fields
        (field (name "Manufacturer Part") "CL05A475MO5NUNC")
        (field (name "Manufacturer") "SAMSUNG(三星)")
        (field (name "Contributor") "LCSC")
      )
      (libsource (lib "easyedapro") (part "4.7uF"))
    )
    (comp (ref "CN5")
      (value "OLED")
      (footprint "easyedapro:FPC-SMD_KH-FG0.5-H2.0-30PIN")
      (fields
        (field (name "Manufacturer Part") "KH-FG0.5-H2.0-30PIN")
        (field (name "Manufacturer") "kinghelm(金航标)")
        (field (name "Contributor") "LCSC")
      )
      (libsource (lib "easyedapro") (part "OLED"))
    )
    (comp (ref "D2")
      (value "1N4148")
      (footprint "easyedapro:SOD-323_L1.8-W1.3-LS2.5-RD")
      (fields (field (name "Manufacturer Part") "1N4148WS") (field (name "Manufacturer") "CJ(江苏长电/长晶)"))
      (libsource (lib "easyedapro") (part "1N4148"))
    )
    (comp (ref "D3")
      (value "1N4148")
      (footprint "easyedapro:SOD-323_L1.8-W1.3-LS2.5-RD")
      (fields (field (name "Manufacturer Part") "1N4148WS") (field (name "Manufacturer") "CJ(江苏长电/长晶)"))
      (libsource (lib "easyedapro") (part "1N4148"))
    )
    (comp (ref "D4")
      (value "SS14")
      (footprint "easyedapro:SMA_L4.2-W2.6-LS5.0-RD_1")
      (fields (field (name "Manufacturer") "MDD(辰达半导体)"))
      (libsource (lib "easyedapro") (part "SS14"))
    )
    (comp (ref "L4")
      (value "4.7uH")
      (footprint "easyedapro:IND-SMD_L4.4-W4.2")
      (fields
        (field (name "Manufacturer Part") "FXL0420-4R7-M")
        (field (name "Manufacturer") "cjiang(长江微电)")
        (field (name "Contributor") "LCSC")
      )
      (libsource (lib "easyedapro") (part "4.7uH"))
    )
    (comp (ref "R17")
      (value "50Ω")
      (footprint "easyedapro:R0402")
      (fields
        (field (name "Manufacturer Part") "RT0402BRE0750RL")
        (field (name "Manufacturer") "YAGEO(国巨)")
        (field (name "Contributor") "lcsc")
      )
      (libsource (lib "easyedapro") (part "50Ω"))
    )
    (comp (ref "R18")
      (value "620kΩ")
      (footprint "easyedapro:R0402")
      (fields
        (field (name "Manufacturer Part") "0402WGJ0624TCE")
        (field (name "Manufacturer") "UNI-ROYAL(厚声)")
      )
      (libsource (lib "easyedapro") (part "620kΩ"))
    )
    (comp (ref "R19")
      (value "30kΩ")
      (footprint "easyedapro:R0402")
      (fields
        (field (name "Manufacturer Part") "0402WGJ0303TCE")
        (field (name "Manufacturer") "UNI-ROYAL(厚声)")
      )
      (libsource (lib "easyedapro") (part "30kΩ"))
    )
    (comp (ref "R20")
      (value "560kΩ")
      (footprint "easyedapro:R0402")
      (fields
        (field (name "Manufacturer Part") "0402WGJ0564TCE")
        (field (name "Manufacturer") "UNI-ROYAL(厚声)")
      )
      (libsource (lib "easyedapro") (part "560kΩ"))
    )
    (comp (ref "U7")
      (value "SX1308")
      (footprint "easyedapro:SOT-23-6_L2.9-W1.6-P0.95-LS2.8-BL")
      (fields (field (name "Manufacturer") "SX(硕芯科技)"))
      (libsource (lib "easyedapro") (part "SX1308"))
    )
  )
  (nets
    (net (code "1") (name "1V5") (class "Default")
      (node (ref "H4") (pin "3") (pinfunction "3_3") (pintype "unspecified"))
      (node (ref "R12") (pin "1") (pinfunction "1_1") (pintype "input"))
    )
    (net (code "2") (name "1V5A") (class "Default")
      (node (ref "C12") (pin "2") (pinfunction "2_2") (pintype "unspecified"))
      (node (ref "H1") (pin "12") (pinfunction "12_12") (pintype "unspecified"))
      (node (ref "L3") (pin "2") (pinfunction "2_2") (pintype "unspecified"))
      (node (ref "U1") (pin "26") (pinfunction "FB2_26") (pintype "unspecified"))
    )
    (net (code "3") (name "2V8") (class "Default")
      (node (ref "H4") (pin "2") (pinfunction "2_2") (pintype "unspecified"))
      (node (ref "R11") (pin "1") (pinfunction "1_1") (pintype "input"))
      (node (ref "R7") (pin "1") (pinfunction "1_1") (pintype "input"))
    )
    (net (code "4") (name "2V8A") (class "Default")
      (node (ref "C11") (pin "2") (pinfunction "2_2") (pintype "unspecified"))
      (node (ref "H1") (pin "13") (pinfunction "13_13") (pintype "unspecified"))
      (node (ref "U1") (pin "18") (pinfunction "ALDO1_18") (pintype "unspecified"))
    )
    (net (code "5") (name "3V3") (class "Default")
      (node (ref "C19") (pin "1") (pinfunction "1_1") (pintype "input"))
      (node (ref "C20") (pin "1") (pinfunction "1_1") (pintype "unspecified"))
      (node (ref "C28") (pin "1") (pinfunction "1_1") (pintype "input"))
      (node (ref "C29") (pin "1") (pinfunction "1_1") (pintype "unspecified"))
      (node (ref "C34") (pin "1") (pinfunction "1_1") (pintype "unspecified"))
      (node (ref "C35") (pin "1") (pinfunction "1_1") (pintype "input"))
      (node (ref "C42") (pin "1") (pinfunction "1_1") (pintype "unspecified"))
      (node (ref "CN5") (pin "14") (pinfunction "14_14") (pintype "unspecified"))
      (node (ref "CN5") (pin "5") (pinfunction "5_5") (pintype "unspecified"))
      (node (ref "H3") (pin "2") (pinfunction "2_2") (pintype "unspecified"))
      (node (ref "H4") (pin "6") (pinfunction "6_6") (pintype "unspecified"))
      (node (ref "R10") (pin "2") (pinfunction "2_2") (pintype "input"))
      (node (ref "R14") (pin "2") (pinfunction "2_2") (pintype "input"))
      (node (ref "R15") (pin "2") (pinfunction "2_2") (pintype "input"))
      (node (ref "U2") (pin "2") (pinfunction "3V3_2") (pintype "unspecified"))
      (node (ref "U3") (pin "2") (pinfunction "GAIN_SLOT_2") (pintype "unspecified"))
      (node (ref "U3") (pin "7") (pinfunction "VDD_7") (pintype "unspecified"))
      (node (ref "U3") (pin "8") (pinfunction "VDD_8") (pintype "unspecified"))
      (node (ref "U6") (pin "10") (pinfunction "VDD_10") (pintype "unspecified"))
      (node (ref "U6") (pin "5") (pinfunction "EN_5") (pintype "unspecified"))
    )
    (net (code "6") (name "3V3A") (class "Default")
      (node (ref "C30") (pin "1") (pinfunction "1_1") (pintype "unspecified"))
      (node (ref "C31") (pin "1") (pinfunction "1_1") (pintype "input"))
      (node (ref "C41") (pin "2") (pinfunction "2_2") (pintype "unspecified"))
      (node (ref "C8") (pin "2") (pinfunction "2_2") (pintype "unspecified"))
      (node (ref "H1") (pin "9") (pinfunction "9_9") (pintype "unspecified"))
      (node (ref "J1") (pin "1") (pinfunction "1_1") (pintype "unspecified"))
      (node (ref "L2") (pin "2") (pinfunction "2_2") (pintype "unspecified"))
      (node (ref "L4") (pin "1") (pinfunction "1_1") (pintype "unspecified"))
      (node (ref "R5") (pin "1") (pinfunction "1_1") (pintype "input"))
      (node (ref "U1") (pin "21") (pinfunction "FB1_21") (pintype "unspecified"))
      (node (ref "U4") (pin "10") (pinfunction "VDDIO_10") (pintype "unspecified"))
      (node (ref "U4") (pin "2") (pinfunction "CS_2") (pintype "unspecified"))
      (node (ref "U4") (pin "3") (pinfunction "SDO/SA0_3") (pintype "unspecified"))
      (node (ref "U4") (pin "9") (pinfunction "VDD_9") (pintype "unspecified"))
      (node (ref "U7") (pin "4") (pinfunction "EN_4") (pintype "unspecified"))
      (node (ref "U7") (pin "5") (pinfunction "VIN_5") (pintype "unspecified"))
    )
    (net (code "7") (name "3V3B") (class "Default")
      (node (ref "C32") (pin "1") (pinfunction "1_1") (pintype "unspecified"))
      (node (ref "H6") (pin "3") (pinfunction "3_3") (pintype "unspecified"))
      (node (ref "U5") (pin "5") (pinfunction "VDD_5") (pintype "unspecified"))
    )
    (net (code "8") (name "ACC_INT") (class "Default")
      (node (ref "H4") (pin "12") (pinfunction "12_12") (pintype "unspecified"))
      (node (ref "U2") (pin "38") (pinfunction "IO2_38") (pintype "unspecified"))
    )
    (net (code "9") (name "ACC_INTA") (class "Default")
      (node (ref "H1") (pin "3") (pinfunction "3_3") (pintype "unspecified"))
      (node (ref "U4") (pin "12") (pinfunction "INT1_12") (pintype "unspecified"))
    )
    (net (code "10") (name "AGND") (class "Default")
      (node (ref "C22") (pin "1") (pinfunction "1_1") (pintype "unspecified"))
      (node (ref "CN2") (pin "2") (pinfunction "2_2") (pintype "unspecified"))
      (node (ref "R13") (pin "2") (pinfunction "2_2") (pintype "input"))
    )
    (net (code "11") (name "AV_2.8V") (class "Default")
      (node (ref "C22") (pin "2") (pinfunction "2_2") (pintype "unspecified"))
      (node (ref "CN2") (pin "4") (pinfunction "4_4") (pintype "unspecified"))
      (node (ref "R11") (pin "2") (pinfunction "2_2") (pintype "input"))
    )
    (net (code "12") (name "BCLK") (class "Default")
      (node (ref "H3") (pin "4") (pinfunction "4_4") (pintype "unspecified"))
      (node (ref "U2") (pin "18") (pinfunction "IO10_18") (pintype "unspecified"))
      (node (ref "U3") (pin "16") (pinfunction "BCLK_16") (pintype "unspecified"))
    )
    (net (code "13") (name "BCLK1") (class "Default")
      (node (ref "H6") (pin "1") (pinfunction "1_1") (pintype "unspecified"))
      (node (ref "U5") (pin "4") (pinfunction "CLK_4") (pintype "unspecified"))
    )
    (net (code "14") (name "BOOT") (class "Default")
      (node (ref "SW3") (pin "1") (pinfunction "1_1") (pintype "unspecified"))
      (node (ref "U2") (pin "27") (pinfunction "IO0/BT_27") (pintype "unspecified"))
    )
    (net (code "15") (name "CAM_PWDN") (class "Default")
      (node (ref "CN2") (pin "8") (pinfunction "8_8") (pintype "unspecified"))
      (node (ref "R9") (pin "1") (pinfunction "1_1") (pintype "input"))
    )
    (net (code "16") (name "CAM_RST") (class "Default")
      (node (ref "CN2") (pin "6") (pinfunction "6_6") (pintype "unspecified"))
      (node (ref "R8") (pin "1") (pinfunction "1_1") (pintype "input"))
    )
    (net (code "17") (name "CHG") (class "Default")
      (node (ref "R6") (pin "1") (pinfunction "1_1") (pintype "input"))
      (node (ref "U1") (pin "1") (pinfunction "CHGLED_1") (pintype "unspecified"))
    )
    (net (code "18") (name "CSI_D0") (class "Default")
      (node (ref "CN2") (pin "19") (pinfunction "19_19") (pintype "unspecified"))
      (node (ref "U2") (pin "32") (pinfunction "IO39_32") (pintype "unspecified"))
    )
    (net (code "19") (name "CSI_D1") (class "Default")
      (node (ref "CN2") (pin "21") (pinfunction "21_21") (pintype "unspecified"))
      (node (ref "U2") (pin "35") (pinfunction "IO42_35") (pintype "unspecified"))
    )
    (net (code "20") (name "CSI_D2") (class "Default")
      (node (ref "CN2") (pin "22") (pinfunction "22_22") (pintype "unspecified"))
      (node (ref "U2") (pin "34") (pinfunction "IO41_34") (pintype "unspecified"))
    )
    (net (code "21") (name "CSI_D3") (class "Default")
      (node (ref "CN2") (pin "20") (pinfunction "20_20") (pintype "unspecified"))
      (node (ref "U2") (pin "33") (pinfunction "IO40_33") (pintype "unspecified"))
    )
    (net (code "22") (name "CSI_D4") (class "Default")
      (node (ref "CN2") (pin "18") (pinfunction "18_18") (pintype "unspecified"))
      (node (ref "U2") (pin "23") (pinfunction "IO21_23") (pintype "unspecified"))
    )
    (net (code "23") (name "CSI_D5") (class "Default")
      (node (ref "CN2") (pin "16") (pinfunction "16_16") (pintype "unspecified"))
      (node (ref "U2") (pin "11") (pinfunction "IO18_11") (pintype "unspecified"))
    )
    (net (code "24") (name "CSI_D6") (class "Default")
      (node (ref "CN2") (pin "14") (pinfunction "14_14") (pintype "unspecified"))
      (node (ref "U2") (pin "10") (pinfunction "IO17_10") (pintype "unspecified"))
    )
    (net (code "25") (name "CSI_D7") (class "Default")
      (node (ref "CN2") (pin "12") (pinfunction "12_12") (pintype "unspecified"))
      (node (ref "U2") (pin "9") (pinfunction "IO16_9") (pintype "unspecified"))
    )
    (net (code "26") (name "CSI_HSYNC") (class "Default")
      (node (ref "CN2") (pin "9") (pinfunction "9_9") (pintype "unspecified"))
      (node (ref "U2") (pin "24") (pinfunction "IO47_24") (pintype "unspecified"))
    )
    (net (code "27") (name "CSI_MCLK") (class "Default")
      (node (ref "CN2") (pin "13") (pinfunction "13_13") (pintype "unspecified"))
      (node (ref "U2") (pin "8") (pinfunction "IO15_8") (pintype "unspecified"))
    )
    (net (code "28") (name "CSI_PCLK") (class "Default")
      (node (ref "CN2") (pin "17") (pinfunction "17_17") (pintype "unspecified"))
      (node (ref "U2") (pin "22") (pinfunction "IO14_22") (pintype "unspecified"))
    )
    (net (code "29") (name "CSI_VSYNC") (class "Default")
      (node (ref "CN2") (pin "7") (pinfunction "7_7") (pintype "unspecified"))
      (node (ref "U2") (pin "25") (pinfunction "IO48_25") (pintype "unspecified"))
    )
    (net (code "30") (name "DIN") (class "Default")
      (node (ref "H3") (pin "3") (pinfunction "3_3") (pintype "unspecified"))
      (node (ref "U2") (pin "20") (pinfunction "IO12_20") (pintype "unspecified"))
      (node (ref "U3") (pin "1") (pinfunction "DIN_1") (pintype "unspecified"))
    )
    (net (code "31") (name "DIN1") (class "Default")
      (node (ref "H6") (pin "2") (pinfunction "2_2") (pintype "unspecified"))
      (node (ref "U5") (pin "1") (pinfunction "DATA_1") (pintype "unspecified"))
    )
    (net (code "32") (name "DISP_CS") (class "Default")
      (node (ref "CN5") (pin "12") (pinfunction "12_12") (pintype "unspecified"))
      (node (ref "U2") (pin "12") (pinfunction "IO8_12") (pintype "unspecified"))
    )
    (net (code "33") (name "DISP_MOSI") (class "Default")
      (node (ref "CN5") (pin "18") (pinfunction "18_18") (pintype "unspecified"))
      (node (ref "U2") (pin "17") (pinfunction "IO9_17") (pintype "unspecified"))
    )
    (net (code "34") (name "DISP_RST") (class "Default")
      (node (ref "CN5") (pin "10") (pinfunction "10_10") (pintype "unspecified"))
      (node (ref "U2") (pin "39") (pinfunction "IO1_39") (pintype "unspecified"))
    )
    (net (code "35") (name "DISP_SCK") (class "Default")
      (node (ref "CN5") (pin "17") (pinfunction "17_17") (pintype "unspecified"))
      (node (ref "U2") (pin "7") (pinfunction "IO7_7") (pintype "unspecified"))
    )
    (net (code "36") (name "DV_1.5V") (class "Default")
      (node (ref "C24") (pin "2") (pinfunction "2_2") (pintype "unspecified"))
      (node (ref "C25") (pin "1") (pinfunction "1_1") (pintype "unspecified"))
      (node (ref "CN2") (pin "10") (pinfunction "10_10") (pintype "unspecified"))
      (node (ref "R12") (pin "2") (pinfunction "2_2") (pintype "input"))
    )
    (net (code "37") (name "DV_2.8V") (class "Default")
      (node (ref "C18") (pin "2") (pinfunction "2_2") (pintype "unspecified"))
      (node (ref "C23") (pin "1") (pinfunction "1_1") (pintype "unspecified"))
      (node (ref "CN2") (pin "11") (pinfunction "11_11") (pintype "unspecified"))
      (node (ref "R7") (pin "2") (pinfunction "2_2") (pintype "input"))
      (node (ref "R8") (pin "2") (pinfunction "2_2") (pintype "input"))
    )
    (net (code "38") (name "EN") (class "Default")
      (node (ref "C21") (pin "1") (pinfunction "1_1") (pintype "unspecified"))
      (node (ref "C26") (pin "2") (pinfunction "2_2") (pintype "unspecified"))
      (node (ref "R10") (pin "1") (pinfunction "1_1") (pintype "input"))
      (node (ref "SW2") (pin "1") (pinfunction "1_1") (pintype "unspecified"))
      (node (ref "U2") (pin "3") (pinfunction "EN_3") (pintype "unspecified"))
    )
    (net (code "39") (name "GND") (class "Default")
      (node (ref "C1") (pin "1") (pinfunction "1_1") (pintype "unspecified"))
      (node (ref "C10") (pin "1") (pinfunction "1_1") (pintype "unspecified"))
      (node (ref "C11") (pin "1") (pinfunction "1_1") (pintype "unspecified"))
      (node (ref "C12") (pin "1") (pinfunction "1_1") (pintype "unspecified"))
      (node (ref "C13") (pin "1") (pinfunction "1_1") (pintype "unspecified"))
      (node (ref "C14") (pin "1") (pinfunction "1_1") (pintype "unspecified"))
      (node (ref "C15") (pin "1") (pinfunction "1_1") (pintype "unspecified"))
      (node (ref "C16") (pin "1") (pinfunction "1_1") (pintype "unspecified"))
      (node (ref "C17") (pin "1") (pinfunction "1_1") (pintype "unspecified"))
      (node (ref "C18") (pin "1") (pinfunction "1_1") (pintype "unspecified"))
      (node (ref "C19") (pin "2") (pinfunction "2_2") (pintype "input"))
      (node (ref "C2") (pin "1") (pinfunction "1_1") (pintype "unspecified"))
      (node (ref "C20") (pin "2") (pinfunction "2_2") (pintype "unspecified"))
      (node (ref "C21") (pin "2") (pinfunction "2_2") (pintype "unspecified"))
      (node (ref "C23") (pin "2") (pinfunction "2_2") (pintype "unspecified"))
      (node (ref "C24") (pin "1") (pinfunction "1_1") (pintype "unspecified"))
      (node (ref "C25") (pin "2") (pinfunction "2_2") (pintype "unspecified"))
      (node (ref "C26") (pin "1") (pinfunction "1_1") (pintype "unspecified"))
      (node (ref "C27") (pin "1") (pinfunction "1_1") (pintype "unspecified"))
      (node (ref "C28") (pin "2") (pinfunction "2_2") (pintype "input"))
      (node (ref "C29") (pin "2") (pinfunction "2_2") (pintype "unspecified"))
      (node (ref "C3") (pin "1") (pinfunction "1_1") (pintype "unspecified"))
      (node (ref "C30") (pin "2") (pinfunction "2_2") (pintype "unspecified"))
      (node (ref "C31") (pin "2") (pinfunction "2_2") (pintype "input"))
      (node (ref "C32") (pin "2") (pinfunction "2_2") (pintype "unspecified"))
      (node (ref "C33") (pin "2") (pinfunction "2_2") (pintype "unspecified"))
      (node (ref "C34") (pin "2") (pinfunction "2_2") (pintype "unspecified"))
      (node (ref "C35") (pin "2") (pinfunction "2_2") (pintype "input"))
      (node (ref "C36") (pin "1") (pinfunction "1_1") (pintype "unspecified"))
      (node (ref "C37") (pin "1") (pinfunction "1_1") (pintype "unspecified"))
      (node (ref "C38") (pin "2") (pinfunction "2_2") (pintype "unspecified"))
      (node (ref "C39") (pin "2") (pinfunction "2_2") (pintype "unspecified"))
      (node (ref "C4") (pin "2") (pinfunction "2_2") (pintype "input"))
      (node (ref "C40") (pin "1") (pinfunction "1_1") (pintype "unspecified"))
      (node (ref "C41") (pin "1") (pinfunction "1_1") (pintype "unspecified"))
      (node (ref "C42") (pin "2") (pinfunction "2_2") (pintype "unspecified"))
      (node (ref "C43") (pin "1") (pinfunction "1_1") (pintype "unspecified"))
      (node (ref "C44") (pin "2") (pinfunction "2_2") (pintype "unspecified"))
      (node (ref "C5") (pin "2") (pinfunction "2_2") (pintype "input"))
      (node (ref "C6") (pin "2") (pinfunction "2_2") (pintype "input"))
      (node (ref "C7") (pin "1") (pinfunction "1_1") (pintype "unspecified"))
      (node (ref "C8") (pin "1") (pinfunction "1_1") (pintype "unspecified"))
      (node (ref "C9") (pin "1") (pinfunction "1_1") (pintype "unspecified"))
      (node (ref "CN1") (pin "1") (pinfunction "1_1") (pintype "unspecified"))
      (node (ref "CN2") (pin "15") (pinfunction "15_15") (pintype "unspecified"))
      (node (ref "CN2") (pin "25") (pinfunction "25_25") (pintype "unspecified"))
      (node (ref "CN2") (pin "26") (pinfunction "26_26") (pintype "unspecified"))
      (node (ref "CN5") (pin "1") (pinfunction "1_1") (pintype "unspecified"))
      (node (ref "CN5") (pin "11") (pinfunction "11_11") (pintype "unspecified"))
      (node (ref "CN5") (pin "13") (pinfunction "13_13") (pintype "unspecified"))
      (node (ref "CN5") (pin "15") (pinfunction "15_15") (pintype "unspecified"))
      (node (ref "CN5") (pin "16") (pinfunction "16_16") (pintype "unspecified"))
      (node (ref "CN5") (pin "20") (pinfunction "20_20") (pintype "unspecified"))
      (node (ref "CN5") (pin "21") (pinfunction "21_21") (pintype "unspecified"))
      (node (ref "CN5") (pin "22") (pinfunction "22_22") (pintype "unspecified"))
      (node (ref "CN5") (pin "23") (pinfunction "23_23") (pintype "unspecified"))
      (node (ref "CN5") (pin "24") (pinfunction "24_24") (pintype "unspecified"))
      (node (ref "CN5") (pin "3") (pinfunction "3_3") (pintype "unspecified"))
      (node (ref "CN5") (pin "30") (pinfunction "30_30") (pintype "unspecified"))
      (node (ref "CN5") (pin "31") (pinfunction "31_31") (pintype "unspecified"))
      (node (ref "CN5") (pin "32") (pinfunction "32_32") (pintype "unspecified"))
      (node (ref "D1") (pin "2") (pinfunction "A_2") (pintype "unspecified"))
      (node (ref "D2") (pin "1") (pinfunction "K_1") (pintype "unspecified"))
      (node (ref "D5") (pin "2") (pinfunction "2_2") (pintype "input"))
      (node (ref "H1") (pin "10") (pinfunction "10_10") (pintype "unspecified"))
      (node (ref "H1") (pin "11") (pinfunction "11_11") (pintype "unspecified"))
      (node (ref "H2") (pin "4") (pinfunction "4_4") (pintype "unspecified"))
      (node (ref "H3") (pin "1") (pinfunction "1_1") (pintype "unspecified"))
      (node (ref "H4") (pin "4") (pinfunction "4_4") (pintype "unspecified"))
      (node (ref "H4") (pin "5") (pinfunction "5_5") (pintype "unspecified"))
      (node (ref "H5") (pin "4") (pinfunction "4_4") (pintype "unspecified"))
      (node (ref "H6") (pin "4") (pinfunction "4_4") (pintype "unspecified"))
      (node (ref "J1") (pin "2") (pinfunction "2_2") (pintype "unspecified"))
      (node (ref "R1") (pin "2") (pinfunction "2_2") (pintype "input"))
      (node (ref "R13") (pin "1") (pinfunction "1_1") (pintype "input"))
      (node (ref "R19") (pin "1") (pinfunction "1_1") (pintype "input"))
      (node (ref "R2") (pin "2") (pinfunction "2_2") (pintype "input"))
      (node (ref "R20") (pin "1") (pinfunction "1_1") (pintype "input"))
      (node (ref "R3") (pin "2") (pinfunction "2_2") (pintype "input"))
      (node (ref "R4") (pin "1") (pinfunction "1_1") (pintype "input"))
      (node (ref "R9") (pin "2") (pinfunction "2_2") (pintype "input"))
      (node (ref "SW1") (pin "1") (pinfunction "1_1") (pintype "input"))
      (node (ref "SW1") (pin "3") (pinfunction "3_3") (pintype "unspecified"))
      (node (ref "SW2") (pin "2") (pinfunction "2_2") (pintype "unspecified"))
      (node (ref "SW3") (pin "2") (pinfunction "2_2") (pintype "unspecified"))
      (node (ref "SW4") (pin "2") (pinfunction "2_2") (pintype "unspecified"))
      (node (ref "U1") (pin "3") (pinfunction "GND_3") (pintype "unspecified"))
      (node (ref "U1") (pin "41") (pinfunction "EP_41") (pintype "unspecified"))
      (node (ref "U2") (pin "1") (pinfunction "GND_1") (pintype "unspecified"))
      (node (ref "U2") (pin "40") (pinfunction "GND_40") (pintype "unspecified"))
      (node (ref "U2") (pin "41") (pinfunction "GND_41") (pintype "unspecified"))
      (node (ref "U3") (pin "11") (pinfunction "GND_11") (pintype "unspecified"))
      (node (ref "U3") (pin "15") (pinfunction "GND_15") (pintype "unspecified"))
      (node (ref "U3") (pin "17") (pinfunction "EP_17") (pintype "unspecified"))
      (node (ref "U3") (pin "3") (pinfunction "GND_3") (pintype "unspecified"))
      (node (ref "U4") (pin "6") (pinfunction "GND_6") (pintype "unspecified"))
      (node (ref "U4") (pin "7") (pinfunction "RES_7") (pintype "unspecified"))
      (node (ref "U4") (pin "8") (pinfunction "GND_8") (pintype "unspecified"))
      (node (ref "U5") (pin "2") (pinfunction "SELECT_2") (pintype "unspecified"))
      (node (ref "U5") (pin "3") (pinfunction "GND_3") (pintype "unspecified"))
      (node (ref "U6") (pin "4") (pinfunction "IN/TRIG_4") (pintype "unspecified"))
      (node (ref "U6") (pin "8") (pinfunction "GND_8") (pintype "unspecified"))
      (node (ref "U7") (pin "2") (pinfunction "GND_2") (pintype "unspecified"))
      (node (ref "USB1") (pin "1") (pinfunction "GND_1") (pintype "unspecified"))
      (node (ref "USB1") (pin "12") (pinfunction "GND_12") (pintype "unspecified"))
    )
    (net (code "40") (name "I2C_SCL") (class "Default")
      (node (ref "CN2") (pin "5") (pinfunction "5_5") (pintype "unspecified"))
      (node (ref "H4") (pin "10") (pinfunction "10_10") (pintype "unspecified"))
      (node (ref "R15") (pin "1") (pinfunction "1_1") (pintype "input"))
      (node (ref "U2") (pin "6") (pinfunction "IO6_6") (pintype "unspecified"))
      (node (ref "U6") (pin "2") (pinfunction "SCL_2") (pintype "unspecified"))
    )
    (net (code "41") (name "I2C_SCLA") (class "Default")
      (node (ref "H1") (pin "5") (pinfunction "5_5") (pintype "unspecified"))
      (node (ref "U1") (pin "40") (pinfunction "SCK_40") (pintype "unspecified"))
      (node (ref "U4") (pin "1") (pinfunction "SCL/SPC_1") (pintype "unspecified"))
    )
    (net (code "42") (name "I2C_SDA") (class "Default")
      (node (ref "CN2") (pin "3") (pinfunction "3_3") (pintype "unspecified"))
      (node (ref "H4") (pin "9") (pinfunction "9_9") (pintype "unspecified"))
      (node (ref "R14") (pin "1") (pinfunction "1_1") (pintype "input"))
      (node (ref "U2") (pin "5") (pinfunction "IO5_5") (pintype "unspecified"))
      (node (ref "U6") (pin "3") (pinfunction "SDA_3") (pintype "unspecified"))
    )
    (net (code "43") (name "I2C_SDAA") (class "Default")
      (node (ref "H1") (pin "6") (pinfunction "6_6") (pintype "unspecified"))
      (node (ref "U1") (pin "39") (pinfunction "SDA_39") (pintype "unspecified"))
      (node (ref "U4") (pin "4") (pinfunction "SDA/SDI/SDO_4") (pintype "unspecified"))
    )
    (net (code "44") (name "LCLK") (class "Default")
      (node (ref "U2") (pin "19") (pinfunction "IO11_19") (pintype "unspecified"))
      (node (ref "U3") (pin "14") (pinfunction "LRCLK_14") (pintype "unspecified"))
    )
    (net (code "45") (name "M+") (class "Default")
      (node (ref "CN4") (pin "2") (pinfunction "2_2") (pintype "unspecified"))
      (node (ref "U6") (pin "7") (pinfunction "OUT+_7") (pintype "unspecified"))
    )
    (net (code "46") (name "M-") (class "Default")
      (node (ref "CN4") (pin "1") (pinfunction "1_1") (pintype "unspecified"))
      (node (ref "U6") (pin "9") (pinfunction "OUT-_9") (pintype "unspecified"))
    )
    (net (code "47") (name "Net-(C6-Pad1)") (class "Default")
      (node (ref "C6") (pin "1") (pinfunction "1_1") (pintype "input"))
      (node (ref "R2") (pin "1") (pinfunction "1_1") (pintype "input"))
      (node (ref "USB1") (pin "13") (pinfunction "SHELL_13") (pintype "unspecified"))
      (node (ref "USB1") (pin "14") (pinfunction "SHELL_14") (pintype "unspecified"))
      (node (ref "USB1") (pin "15") (pinfunction "SHELL_15") (pintype "unspecified"))
      (node (ref "USB1") (pin "16") (pinfunction "SHELL_16") (pintype "unspecified"))
    )
    (net (code "48") (name "Net-(C38-Pad1)") (class "Default")
      (node (ref "C38") (pin "1") (pinfunction "1_1") (pintype "unspecified"))
      (node (ref "CN5") (pin "28") (pinfunction "28_28") (pintype "unspecified"))
    )
    (net (code "49") (name "Net-(C39-Pad1)") (class "Default")
      (node (ref "C39") (pin "1") (pinfunction "1_1") (pintype "unspecified"))
      (node (ref "CN5") (pin "27") (pinfunction "27_27") (pintype "unspecified"))
    )
    (net (code "50") (name "Net-(C43-Pad2)") (class "Default")
      (node (ref "C43") (pin "2") (pinfunction "2_2") (pintype "unspecified"))
      (node (ref "C44") (pin "1") (pinfunction "1_1") (pintype "unspecified"))
      (node (ref "CN5") (pin "4") (pinfunction "4_4") (pintype "unspecified"))
    )
    (net (code "51") (name "Net-(CN5-Pad9)") (class "Default")
      (node (ref "CN5") (pin "9") (pinfunction "9_9") (pintype "unspecified"))
      (node (ref "R20") (pin "2") (pinfunction "2_2") (pintype "input"))
    )
    (net (code "52") (name "Net-(CN5-Pad26)") (class "Default")
      (node (ref "CN5") (pin "26") (pinfunction "26_26") (pintype "unspecified"))
      (node (ref "R17") (pin "2") (pinfunction "2_2") (pintype "unspecified"))
    )
    (net (code "53") (name "Net-(D2-A)") (class "Default")
      (node (ref "D2") (pin "2") (pinfunction "A_2") (pintype "unspecified"))
      (node (ref "D3") (pin "1") (pinfunction "K_1") (pintype "unspecified"))
    )
    (net (code "54") (name "Net-(D3-A)") (class "Default")
      (node (ref "D3") (pin "2") (pinfunction "A_2") (pintype "unspecified"))
      (node (ref "R17") (pin "1") (pinfunction "1_1") (pintype "unspecified"))
    )
    (net (code "55") (name "Net-(D4-A)") (class "Default")
      (node (ref "D4") (pin "2") (pinfunction "A_2") (pintype "unspecified"))
      (node (ref "L4") (pin "2") (pinfunction "2_2") (pintype "unspecified"))
      (node (ref "U7") (pin "1") (pinfunction "SW_1") (pintype "unspecified"))
    )
    (net (code "56") (name "Net-(LED1-K)") (class "Default")
      (node (ref "LED1") (pin "1") (pinfunction "K_1") (pintype "unspecified"))
      (node (ref "R6") (pin "2") (pinfunction "2_2") (pintype "input"))
    )
    (net (code "57") (name "Net-(U1-BAT)") (class "Default")
      (node (ref "C17") (pin "2") (pinfunction "2_2") (pintype "unspecified"))
      (node (ref "CN1") (pin "2") (pinfunction "2_2") (pintype "unspecified"))
      (node (ref "U1") (pin "33") (pinfunction "BAT_33") (pintype "unspecified"))
    )
    (net (code "58") (name "Net-(U1-LX1)") (class "Default")
      (node (ref "L2") (pin "1") (pinfunction "1_1") (pintype "unspecified"))
      (node (ref "U1") (pin "22") (pinfunction "LX1_22") (pintype "unspecified"))
    )
    (net (code "59") (name "Net-(U1-LX2)") (class "Default")
      (node (ref "L3") (pin "1") (pinfunction "1_1") (pintype "unspecified"))
      (node (ref "U1") (pin "25") (pinfunction "LX2_25") (pintype "unspecified"))
    )
    (net (code "60") (name "Net-(U1-SW)") (class "Default")
      (node (ref "L1") (pin "1") (pinfunction "1_1") (pintype "unspecified"))
      (node (ref "U1") (pin "35") (pinfunction "SW_35") (pintype "unspecified"))
    )
    (net (code "61") (name "Net-(U1-TS)") (class "Default")
      (node (ref "R4") (pin "2") (pinfunction "2_2") (pintype "input"))
      (node (ref "U1") (pin "31") (pinfunction "TS_31") (pintype "unspecified"))
    )
    (net (code "62") (name "Net-(U1-VMID)") (class "Default")
      (node (ref "C5") (pin "1") (pinfunction "1_1") (pintype "input"))
      (node (ref "U1") (pin "36") (pinfunction "VMID_36") (pintype "unspecified"))
    )
    (net (code "63") (name "Net-(U1-VREF)") (class "Default")
      (node (ref "C1") (pin "2") (pinfunction "2_2") (pintype "unspecified"))
      (node (ref "U1") (pin "2") (pinfunction "VREF_2") (pintype "unspecified"))
    )
    (net (code "64") (name "Net-(U1-VRTC)") (class "Default")
      (node (ref "C16") (pin "2") (pinfunction "2_2") (pintype "unspecified"))
      (node (ref "U1") (pin "28") (pinfunction "VRTC_28") (pintype "unspecified"))
    )
    (net (code "65") (name "Net-(U3-OUTN)") (class "Default")
      (node (ref "CN3") (pin "1") (pinfunction "1_1") (pintype "unspecified"))
      (node (ref "U3") (pin "10") (pinfunction "OUTN_10") (pintype "unspecified"))
    )
    (net (code "66") (name "Net-(U3-OUTP)") (class "Default")
      (node (ref "CN3") (pin "2") (pinfunction "2_2") (pintype "unspecified"))
      (node (ref "U3") (pin "9") (pinfunction "OUTP_9") (pintype "unspecified"))
    )
    (net (code "67") (name "Net-(U3-SD_MODE#)") (class "Default")
      (node (ref "R16") (pin "1") (pinfunction "1_1") (pintype "input"))
      (node (ref "U3") (pin "4") (pinfunction "SD_MODE#_4") (pintype "unspecified"))
    )
    (net (code "68") (name "Net-(U6-REG)") (class "Default")
      (node (ref "C33") (pin "1") (pinfunction "1_1") (pintype "unspecified"))
      (node (ref "U6") (pin "1") (pinfunction "REG_1") (pintype "unspecified"))
    )
    (net (code "69") (name "Net-(U7-FB)") (class "Default")
      (node (ref "R18") (pin "1") (pinfunction "1_1") (pintype "input"))
      (node (ref "R19") (pin "2") (pinfunction "2_2") (pintype "input"))
      (node (ref "U7") (pin "3") (pinfunction "FB_3") (pintype "unspecified"))
    )
    (net (code "70") (name "Net-(USB1-CC1)") (class "Default")
      (node (ref "R1") (pin "1") (pinfunction "1_1") (pintype "input"))
      (node (ref "USB1") (pin "4") (pinfunction "CC1_4") (pintype "unspecified"))
    )
    (net (code "71") (name "Net-(USB1-CC2)") (class "Default")
      (node (ref "R3") (pin "1") (pinfunction "1_1") (pintype "input"))
      (node (ref "USB1") (pin "10") (pinfunction "CC2_10") (pintype "unspecified"))
    )
    (net (code "72") (name "PWRON") (class "Default")
      (node (ref "D1") (pin "1") (pinfunction "C_1") (pintype "unspecified"))
      (node (ref "SW1") (pin "2") (pinfunction "2_2") (pintype "input"))
      (node (ref "U1") (pin "30") (pinfunction "PWRON_30") (pintype "unspecified"))
    )
    (net (code "73") (name "PWR_IRQ") (class "Default")
      (node (ref "H1") (pin "4") (pinfunction "4_4") (pintype "unspecified"))
      (node (ref "R5") (pin "2") (pinfunction "2_2") (pintype "input"))
      (node (ref "U1") (pin "38") (pinfunction "IRQ_38") (pintype "unspecified"))
    )
    (net (code "74") (name "PWR_IRQA") (class "Default")
      (node (ref "H4") (pin "11") (pinfunction "11_11") (pintype "unspecified"))
      (node (ref "U2") (pin "4") (pinfunction "IO4_4") (pintype "unspecified"))
    )
    (net (code "75") (name "RXD") (class "Default")
      (node (ref "H4") (pin "7") (pinfunction "7_7") (pintype "unspecified"))
      (node (ref "U2") (pin "36") (pinfunction "RXD0_36") (pintype "unspecified"))
    )
    (net (code "76") (name "RXDA") (class "Default")
      (node (ref "H1") (pin "8") (pinfunction "8_8") (pintype "unspecified"))
      (node (ref "J1") (pin "3") (pinfunction "3_3") (pintype "unspecified"))
    )
    (net (code "77") (name "SD") (class "Default")
      (node (ref "R16") (pin "2") (pinfunction "2_2") (pintype "input"))
      (node (ref "U2") (pin "21") (pinfunction "IO13_21") (pintype "unspecified"))
    )
    (net (code "78") (name "TXD") (class "Default")
      (node (ref "H4") (pin "8") (pinfunction "8_8") (pintype "unspecified"))
      (node (ref "U2") (pin "37") (pinfunction "TXD0_37") (pintype "unspecified"))
    )
    (net (code "79") (name "TXDA") (class "Default")
      (node (ref "H1") (pin "7") (pinfunction "7_7") (pintype "unspecified"))
      (node (ref "J1") (pin "4") (pinfunction "4_4") (pintype "unspecified"))
    )
    (net (code "80") (name "USB_D_N") (class "Default")
      (node (ref "D5") (pin "4") (pinfunction "4_4") (pintype "input"))
      (node (ref "USB1") (pin "5") (pinfunction "DN2_5") (pintype "unspecified"))
      (node (ref "USB1") (pin "7") (pinfunction "DN1_7") (pintype "unspecified"))
    )
    (net (code "81") (name "USB_D_P") (class "Default")
      (node (ref "D5") (pin "6") (pinfunction "6_6") (pintype "input"))
      (node (ref "USB1") (pin "6") (pinfunction "DP1_6") (pintype "unspecified"))
      (node (ref "USB1") (pin "8") (pinfunction "DP2_8") (pintype "unspecified"))
    )
    (net (code "82") (name "USB_N") (class "Default")
      (node (ref "D5") (pin "3") (pinfunction "3_3") (pintype "input"))
      (node (ref "H1") (pin "2") (pinfunction "2_2") (pintype "unspecified"))
    )
    (net (code "83") (name "USB_P") (class "Default")
      (node (ref "D5") (pin "1") (pinfunction "1_1") (pintype "input"))
      (node (ref "H1") (pin "1") (pinfunction "1_1") (pintype "unspecified"))
    )
    (net (code "84") (name "USER_BTT") (class "Default")
      (node (ref "H2") (pin "1") (pinfunction "1_1") (pintype "unspecified"))
      (node (ref "U2") (pin "31") (pinfunction "IO38_31") (pintype "unspecified"))
    )
    (net (code "85") (name "USER_BTT1") (class "Default")
      (node (ref "C27") (pin "2") (pinfunction "2_2") (pintype "unspecified"))
      (node (ref "H5") (pin "1") (pinfunction "1_1") (pintype "unspecified"))
      (node (ref "SW4") (pin "1") (pinfunction "1_1") (pintype "unspecified"))
    )
    (net (code "86") (name "US_D_N") (class "Default")
      (node (ref "H4") (pin "13") (pinfunction "13_13") (pintype "unspecified"))
      (node (ref "U2") (pin "13") (pinfunction "IO19/DN_13") (pintype "unspecified"))
    )
    (net (code "87") (name "US_D_P") (class "Default")
      (node (ref "H4") (pin "14") (pinfunction "14_14") (pintype "unspecified"))
      (node (ref "U2") (pin "14") (pinfunction "IO20/DP_14") (pintype "unspecified"))
    )
    (net (code "88") (name "VBUS") (class "Default")
      (node (ref "C4") (pin "1") (pinfunction "1_1") (pintype "input"))
      (node (ref "D5") (pin "5") (pinfunction "5_5") (pintype "input"))
      (node (ref "U1") (pin "37") (pinfunction "VBUS_37") (pintype "unspecified"))
      (node (ref "USB1") (pin "11") (pinfunction "VBUS_11") (pintype "unspecified"))
      (node (ref "USB1") (pin "2") (pinfunction "VBUS_2") (pintype "unspecified"))
    )
    (net (code "89") (name "VPP") (class "Default")
      (node (ref "C36") (pin "2") (pinfunction "2_2") (pintype "unspecified"))
      (node (ref "C37") (pin "2") (pinfunction "2_2") (pintype "unspecified"))
      (node (ref "CN5") (pin "29") (pinfunction "29_29") (pintype "unspecified"))
      (node (ref "H4") (pin "1") (pinfunction "1_1") (pintype "unspecified"))
    )
    (net (code "90") (name "VPPA") (class "Default")
      (node (ref "C40") (pin "2") (pinfunction "2_2") (pintype "unspecified"))
      (node (ref "D4") (pin "1") (pinfunction "K_1") (pintype "unspecified"))
      (node (ref "H1") (pin "14") (pinfunction "14_14") (pintype "unspecified"))
      (node (ref "R18") (pin "2") (pinfunction "2_2") (pintype "input"))
    )
    (net (code "91") (name "VSYS") (class "Default")
      (node (ref "C10") (pin "2") (pinfunction "2_2") (pintype "unspecified"))
      (node (ref "C13") (pin "2") (pinfunction "2_2") (pintype "unspecified"))
      (node (ref "C14") (pin "2") (pinfunction "2_2") (pintype "unspecified"))
      (node (ref "C15") (pin "2") (pinfunction "2_2") (pintype "unspecified"))
      (node (ref "C2") (pin "2") (pinfunction "2_2") (pintype "unspecified"))
      (node (ref "C3") (pin "2") (pinfunction "2_2") (pintype "unspecified"))
      (node (ref "C7") (pin "2") (pinfunction "2_2") (pintype "unspecified"))
      (node (ref "C9") (pin "2") (pinfunction "2_2") (pintype "unspecified"))
      (node (ref "L1") (pin "2") (pinfunction "2_2") (pintype "unspecified"))
      (node (ref "LED1") (pin "2") (pinfunction "A_2") (pintype "unspecified"))
      (node (ref "U1") (pin "13") (pinfunction "BLDOIN_13") (pintype "unspecified"))
      (node (ref "U1") (pin "17") (pinfunction "ALDOIN_17") (pintype "unspecified"))
      (node (ref "U1") (pin "23") (pinfunction "VIN1_23") (pintype "unspecified"))
      (node (ref "U1") (pin "24") (pinfunction "VIN2_24") (pintype "unspecified"))
      (node (ref "U1") (pin "34") (pinfunction "VSYS_34") (pintype "unspecified"))
      (node (ref "U1") (pin "6") (pinfunction "VIN3_6") (pintype "unspecified"))
      (node (ref "U1") (pin "7") (pinfunction "VIN4_7") (pintype "unspecified"))
    )
    (net (code "92") (name "unconnected-(CN2-Pad1)") (class "Default")
      (node (ref "CN2") (pin "1") (pinfunction "1_1") (pintype "unspecified+no_connect"))
    )
    (net (code "93") (name "unconnected-(CN2-Pad23)") (class "Default")
      (node (ref "CN2") (pin "23") (pinfunction "23_23") (pintype "unspecified+no_connect"))
    )
    (net (code "94") (name "unconnected-(CN2-Pad24)") (class "Default")
      (node (ref "CN2") (pin "24") (pinfunction "24_24") (pintype "unspecified+no_connect"))
    )
    (net (code "95") (name "unconnected-(CN5-Pad2)") (class "Default")
      (node (ref "CN5") (pin "2") (pinfunction "2_2") (pintype "unspecified+no_connect"))
    )
    (net (code "96") (name "unconnected-(CN5-Pad6)") (class "Default")
      (node (ref "CN5") (pin "6") (pinfunction "6_6") (pintype "unspecified+no_connect"))
    )
    (net (code "97") (name "unconnected-(CN5-Pad7)") (class "Default")
      (node (ref "CN5") (pin "7") (pinfunction "7_7") (pintype "unspecified+no_connect"))
    )
    (net (code "98") (name "unconnected-(CN5-Pad8)") (class "Default")
      (node (ref "CN5") (pin "8") (pinfunction "8_8") (pintype "unspecified+no_connect"))
    )
    (net (code "99") (name "unconnected-(CN5-Pad19)") (class "Default")
      (node (ref "CN5") (pin "19") (pinfunction "19_19") (pintype "unspecified+no_connect"))
    )
    (net (code "100") (name "unconnected-(CN5-Pad25)") (class "Default")
      (node (ref "CN5") (pin "25") (pinfunction "25_25") (pintype "unspecified+no_connect"))
    )
    (net (code "101") (name "unconnected-(H2-Pad2)") (class "Default")
      (node (ref "H2") (pin "2") (pinfunction "2_2") (pintype "unspecified+no_connect"))
    )
    (net (code "102") (name "unconnected-(H2-Pad3)") (class "Default")
      (node (ref "H2") (pin "3") (pinfunction "3_3") (pintype "unspecified+no_connect"))
    )
    (net (code "103") (name "unconnected-(H5-Pad2)") (class "Default")
      (node (ref "H5") (pin "2") (pinfunction "2_2") (pintype "unspecified+no_connect"))
    )
    (net (code "104") (name "unconnected-(H5-Pad3)") (class "Default")
      (node (ref "H5") (pin "3") (pinfunction "3_3") (pintype "unspecified+no_connect"))
    )
    (net (code "105") (name "unconnected-(U1-ALDO2-Pad19)") (class "Default")
      (node (ref "U1") (pin "19") (pinfunction "ALDO2_19") (pintype "unspecified+no_connect"))
    )
    (net (code "106") (name "unconnected-(U1-ALDO3-Pad16)") (class "Default")
      (node (ref "U1") (pin "16") (pinfunction "ALDO3_16") (pintype "unspecified+no_connect"))
    )
    (net (code "107") (name "unconnected-(U1-ALDO4-Pad15)") (class "Default")
      (node (ref "U1") (pin "15") (pinfunction "ALDO4_15") (pintype "unspecified+no_connect"))
    )
    (net (code "108") (name "unconnected-(U1-BLDO1-Pad12)") (class "Default")
      (node (ref "U1") (pin "12") (pinfunction "BLDO1_12") (pintype "unspecified+no_connect"))
    )
    (net (code "109") (name "unconnected-(U1-BLDO2-Pad14)") (class "Default")
      (node (ref "U1") (pin "14") (pinfunction "BLDO2_14") (pintype "unspecified+no_connect"))
    )
    (net (code "110") (name "unconnected-(U1-CPULDOS-Pad10)") (class "Default")
      (node (ref "U1") (pin "10") (pinfunction "CPULDOS_10") (pintype "unspecified+no_connect"))
    )
    (net (code "111") (name "unconnected-(U1-DLDO1{slash}DC1SW-Pad20)") (class "Default")
      (node (ref "U1") (pin "20") (pinfunction "DLDO1/DC1SW_20") (pintype "unspecified+no_connect"))
    )
    (net (code "112") (name "unconnected-(U1-DLDO2{slash}DC4SW-Pad11)") (class "Default")
      (node (ref "U1") (pin "11") (pinfunction "DLDO2/DC4SW_11") (pintype "unspecified+no_connect"))
    )
    (net (code "113") (name "unconnected-(U1-FB3-Pad4)") (class "Default")
      (node (ref "U1") (pin "4") (pinfunction "FB3_4") (pintype "unspecified+no_connect"))
    )
    (net (code "114") (name "unconnected-(U1-FB4-Pad9)") (class "Default")
      (node (ref "U1") (pin "9") (pinfunction "FB4_9") (pintype "unspecified+no_connect"))
    )
    (net (code "115") (name "unconnected-(U1-GPIO1{slash}FB5{slash}RTC{slash}LDO2-Pad32)") (class "Default")
      (node (ref "U1") (pin "32") (pinfunction "GPIO1/FB5/RTC/LDO2_32") (pintype "unspecified+no_connect"))
    )
    (net (code "116") (name "unconnected-(U1-LX3-Pad5)") (class "Default")
      (node (ref "U1") (pin "5") (pinfunction "LX3_5") (pintype "unspecified+no_connect"))
    )
    (net (code "117") (name "unconnected-(U1-LX4-Pad8)") (class "Default")
      (node (ref "U1") (pin "8") (pinfunction "LX4_8") (pintype "unspecified+no_connect"))
    )
    (net (code "118") (name "unconnected-(U1-PWROK-Pad29)") (class "Default")
      (node (ref "U1") (pin "29") (pinfunction "PWROK_29") (pintype "unspecified+no_connect"))
    )
    (net (code "119") (name "unconnected-(U1-VBACKUP-Pad27)") (class "Default")
      (node (ref "U1") (pin "27") (pinfunction "VBACKUP_27") (pintype "unspecified+no_connect"))
    )
    (net (code "120") (name "unconnected-(U2-IO3-Pad15)") (class "Default")
      (node (ref "U2") (pin "15") (pinfunction "IO3_15") (pintype "unspecified+no_connect"))
    )
    (net (code "121") (name "unconnected-(U2-IO35-Pad28)") (class "Default")
      (node (ref "U2") (pin "28") (pinfunction "IO35_28") (pintype "unspecified+no_connect"))
    )
    (net (code "122") (name "unconnected-(U2-IO36-Pad29)") (class "Default")
      (node (ref "U2") (pin "29") (pinfunction "IO36_29") (pintype "unspecified+no_connect"))
    )
    (net (code "123") (name "unconnected-(U2-IO37-Pad30)") (class "Default")
      (node (ref "U2") (pin "30") (pinfunction "IO37_30") (pintype "unspecified+no_connect"))
    )
    (net (code "124") (name "unconnected-(U2-IO45-Pad26)") (class "Default")
      (node (ref "U2") (pin "26") (pinfunction "IO45_26") (pintype "unspecified+no_connect"))
    )
    (net (code "125") (name "unconnected-(U2-IO46-Pad16)") (class "Default")
      (node (ref "U2") (pin "16") (pinfunction "IO46_16") (pintype "unspecified+no_connect"))
    )
    (net (code "126") (name "unconnected-(U3-N.C.-Pad5)") (class "Default")
      (node (ref "U3") (pin "5") (pinfunction "N.C._5") (pintype "unspecified+no_connect"))
    )
    (net (code "127") (name "unconnected-(U3-N.C.-Pad6)") (class "Default")
      (node (ref "U3") (pin "6") (pinfunction "N.C._6") (pintype "unspecified+no_connect"))
    )
    (net (code "128") (name "unconnected-(U3-N.C.-Pad12)") (class "Default")
      (node (ref "U3") (pin "12") (pinfunction "N.C._12") (pintype "unspecified+no_connect"))
    )
    (net (code "129") (name "unconnected-(U3-N.C.-Pad13)") (class "Default")
      (node (ref "U3") (pin "13") (pinfunction "N.C._13") (pintype "unspecified+no_connect"))
    )
    (net (code "130") (name "unconnected-(U4-INT2-Pad11)") (class "Default")
      (node (ref "U4") (pin "11") (pinfunction "INT2_11") (pintype "unspecified+no_connect"))
    )
    (net (code "131") (name "unconnected-(U4-NC-Pad5)") (class "Default")
      (node (ref "U4") (pin "5") (pinfunction "NC_5") (pintype "unspecified+no_connect"))
    )
    (net (code "132") (name "unconnected-(U6-VDD{slash}NC-Pad6)") (class "Default")
      (node (ref "U6") (pin "6") (pinfunction "VDD/NC_6") (pintype "unspecified+no_connect"))
    )
    (net (code "133") (name "unconnected-(U7-NC-Pad6)") (class "Default")
      (node (ref "U7") (pin "6") (pinfunction "NC_6") (pintype "unspecified+no_connect"))
    )
    (net (code "134") (name "unconnected-(USB1-SBU1-Pad9)") (class "Default")
      (node (ref "USB1") (pin "9") (pinfunction "SBU1_9") (pintype "unspecified+no_connect"))
    )
    (net (code "135") (name "unconnected-(USB1-SBU2-Pad3)") (class "Default")
      (node (ref "USB1") (pin "3") (pinfunction "SBU2_3") (pintype "unspecified+no_connect"))
    )
  )
)
